# piezopiano.net
KiCad netlist of a schematic drawn in EAGLE
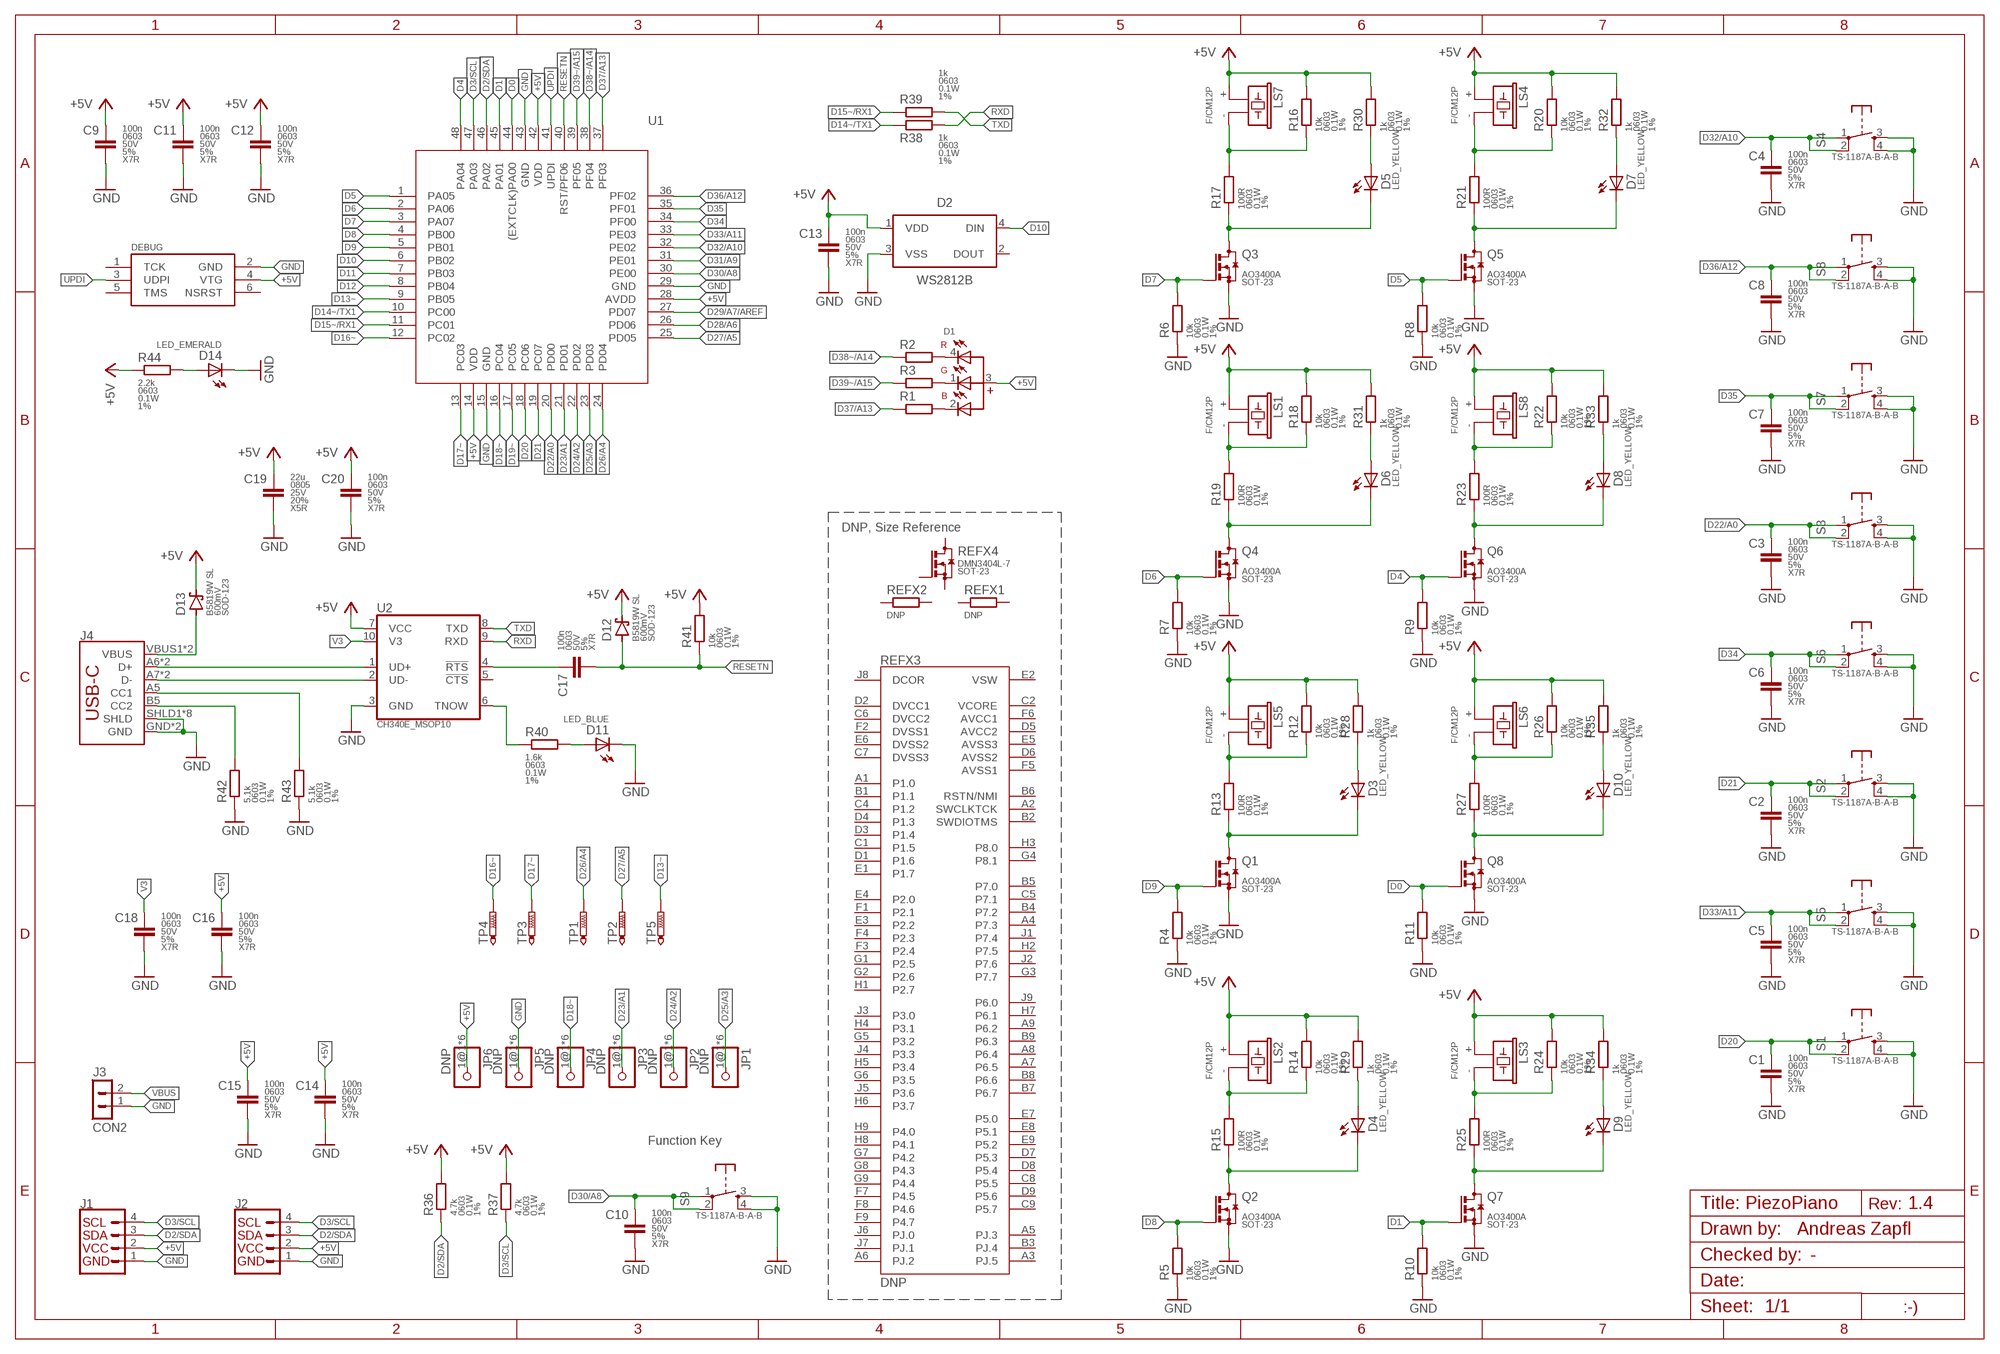
[diagram p0: schematic, sheet 1]

(export (version "E")
  (design (tool "Eeschema 10.0.6"))
  (components
    (comp (ref "C1")
      (value "100n")
      (footprint "eagle-import:C0603")
      (fields
        (field (name "PACKAGE-IN") "0603")
        (field (name "VOLTAGE") "50V")
        (field (name "TOLERANCE") "5%")
        (field (name "DIELECTRIC") "X7R")
        (field (name "MF") "Yageo")
        (field (name "MPN") "CC0603JRX7R9BB104")
      )
      (libsource (lib "eagle-import") (part "100NF-0603-50V-5%"))
    )
    (comp (ref "C2")
      (value "100n")
      (footprint "eagle-import:C0603")
      (fields
        (field (name "PACKAGE-IN") "0603")
        (field (name "VOLTAGE") "50V")
        (field (name "TOLERANCE") "5%")
        (field (name "DIELECTRIC") "X7R")
        (field (name "MF") "Yageo")
        (field (name "MPN") "CC0603JRX7R9BB104")
      )
      (libsource (lib "eagle-import") (part "100NF-0603-50V-5%"))
    )
    (comp (ref "C3")
      (value "100n")
      (footprint "eagle-import:C0603")
      (fields
        (field (name "PACKAGE-IN") "0603")
        (field (name "VOLTAGE") "50V")
        (field (name "TOLERANCE") "5%")
        (field (name "DIELECTRIC") "X7R")
        (field (name "MF") "Yageo")
        (field (name "MPN") "CC0603JRX7R9BB104")
      )
      (libsource (lib "eagle-import") (part "100NF-0603-50V-5%"))
    )
    (comp (ref "C4")
      (value "100n")
      (footprint "eagle-import:C0603")
      (fields
        (field (name "PACKAGE-IN") "0603")
        (field (name "VOLTAGE") "50V")
        (field (name "TOLERANCE") "5%")
        (field (name "DIELECTRIC") "X7R")
        (field (name "MF") "Yageo")
        (field (name "MPN") "CC0603JRX7R9BB104")
      )
      (libsource (lib "eagle-import") (part "100NF-0603-50V-5%"))
    )
    (comp (ref "C5")
      (value "100n")
      (footprint "eagle-import:C0603")
      (fields
        (field (name "PACKAGE-IN") "0603")
        (field (name "VOLTAGE") "50V")
        (field (name "TOLERANCE") "5%")
        (field (name "DIELECTRIC") "X7R")
        (field (name "MF") "Yageo")
        (field (name "MPN") "CC0603JRX7R9BB104")
      )
      (libsource (lib "eagle-import") (part "100NF-0603-50V-5%"))
    )
    (comp (ref "C6")
      (value "100n")
      (footprint "eagle-import:C0603")
      (fields
        (field (name "PACKAGE-IN") "0603")
        (field (name "VOLTAGE") "50V")
        (field (name "TOLERANCE") "5%")
        (field (name "DIELECTRIC") "X7R")
        (field (name "MF") "Yageo")
        (field (name "MPN") "CC0603JRX7R9BB104")
      )
      (libsource (lib "eagle-import") (part "100NF-0603-50V-5%"))
    )
    (comp (ref "C7")
      (value "100n")
      (footprint "eagle-import:C0603")
      (fields
        (field (name "PACKAGE-IN") "0603")
        (field (name "VOLTAGE") "50V")
        (field (name "TOLERANCE") "5%")
        (field (name "DIELECTRIC") "X7R")
        (field (name "MF") "Yageo")
        (field (name "MPN") "CC0603JRX7R9BB104")
      )
      (libsource (lib "eagle-import") (part "100NF-0603-50V-5%"))
    )
    (comp (ref "C8")
      (value "100n")
      (footprint "eagle-import:C0603")
      (fields
        (field (name "PACKAGE-IN") "0603")
        (field (name "VOLTAGE") "50V")
        (field (name "TOLERANCE") "5%")
        (field (name "DIELECTRIC") "X7R")
        (field (name "MF") "Yageo")
        (field (name "MPN") "CC0603JRX7R9BB104")
      )
      (libsource (lib "eagle-import") (part "100NF-0603-50V-5%"))
    )
    (comp (ref "C9")
      (value "100n")
      (footprint "eagle-import:C0603")
      (fields
        (field (name "PACKAGE-IN") "0603")
        (field (name "VOLTAGE") "50V")
        (field (name "TOLERANCE") "5%")
        (field (name "DIELECTRIC") "X7R")
        (field (name "MF") "Yageo")
        (field (name "MPN") "CC0603JRX7R9BB104")
      )
      (libsource (lib "eagle-import") (part "100NF-0603-50V-5%"))
    )
    (comp (ref "C10")
      (value "100n")
      (footprint "eagle-import:C0603")
      (fields
        (field (name "PACKAGE-IN") "0603")
        (field (name "VOLTAGE") "50V")
        (field (name "TOLERANCE") "5%")
        (field (name "DIELECTRIC") "X7R")
        (field (name "MF") "Yageo")
        (field (name "MPN") "CC0603JRX7R9BB104")
      )
      (libsource (lib "eagle-import") (part "100NF-0603-50V-5%"))
    )
    (comp (ref "C11")
      (value "100n")
      (footprint "eagle-import:C0603")
      (fields
        (field (name "PACKAGE-IN") "0603")
        (field (name "VOLTAGE") "50V")
        (field (name "TOLERANCE") "5%")
        (field (name "DIELECTRIC") "X7R")
        (field (name "MF") "Yageo")
        (field (name "MPN") "CC0603JRX7R9BB104")
      )
      (libsource (lib "eagle-import") (part "100NF-0603-50V-5%"))
    )
    (comp (ref "C12")
      (value "100n")
      (footprint "eagle-import:C0603")
      (fields
        (field (name "PACKAGE-IN") "0603")
        (field (name "VOLTAGE") "50V")
        (field (name "TOLERANCE") "5%")
        (field (name "DIELECTRIC") "X7R")
        (field (name "MF") "Yageo")
        (field (name "MPN") "CC0603JRX7R9BB104")
      )
      (libsource (lib "eagle-import") (part "100NF-0603-50V-5%"))
    )
    (comp (ref "C13")
      (value "100n")
      (footprint "eagle-import:C0603")
      (fields
        (field (name "PACKAGE-IN") "0603")
        (field (name "VOLTAGE") "50V")
        (field (name "TOLERANCE") "5%")
        (field (name "DIELECTRIC") "X7R")
        (field (name "MF") "Yageo")
        (field (name "MPN") "CC0603JRX7R9BB104")
      )
      (libsource (lib "eagle-import") (part "100NF-0603-50V-5%"))
    )
    (comp (ref "C14")
      (value "100n")
      (footprint "eagle-import:C0603")
      (fields
        (field (name "PACKAGE-IN") "0603")
        (field (name "VOLTAGE") "50V")
        (field (name "TOLERANCE") "5%")
        (field (name "DIELECTRIC") "X7R")
        (field (name "MF") "Yageo")
        (field (name "MPN") "CC0603JRX7R9BB104")
      )
      (libsource (lib "eagle-import") (part "100NF-0603-50V-5%"))
    )
    (comp (ref "C15")
      (value "100n")
      (footprint "eagle-import:C0603")
      (fields
        (field (name "PACKAGE-IN") "0603")
        (field (name "VOLTAGE") "50V")
        (field (name "TOLERANCE") "5%")
        (field (name "DIELECTRIC") "X7R")
        (field (name "MF") "Yageo")
        (field (name "MPN") "CC0603JRX7R9BB104")
      )
      (libsource (lib "eagle-import") (part "100NF-0603-50V-5%"))
    )
    (comp (ref "C16")
      (value "100n")
      (footprint "eagle-import:C0603")
      (fields
        (field (name "PACKAGE-IN") "0603")
        (field (name "VOLTAGE") "50V")
        (field (name "TOLERANCE") "5%")
        (field (name "DIELECTRIC") "X7R")
        (field (name "MF") "Yageo")
        (field (name "MPN") "CC0603JRX7R9BB104")
      )
      (libsource (lib "eagle-import") (part "100NF-0603-50V-5%"))
    )
    (comp (ref "C17")
      (value "100n")
      (footprint "eagle-import:C0603")
      (fields
        (field (name "PACKAGE-IN") "0603")
        (field (name "VOLTAGE") "50V")
        (field (name "TOLERANCE") "5%")
        (field (name "DIELECTRIC") "X7R")
        (field (name "MF") "Yageo")
        (field (name "MPN") "CC0603JRX7R9BB104")
      )
      (libsource (lib "eagle-import") (part "100NF-0603-50V-5%"))
    )
    (comp (ref "C18")
      (value "100n")
      (footprint "eagle-import:C0603")
      (fields
        (field (name "PACKAGE-IN") "0603")
        (field (name "VOLTAGE") "50V")
        (field (name "TOLERANCE") "5%")
        (field (name "DIELECTRIC") "X7R")
        (field (name "MF") "Yageo")
        (field (name "MPN") "CC0603JRX7R9BB104")
      )
      (libsource (lib "eagle-import") (part "100NF-0603-50V-5%"))
    )
    (comp (ref "C19")
      (value "22u")
      (footprint "eagle-import:C0805")
      (fields
        (field (name "PACKAGE-IN") "0805")
        (field (name "VOLTAGE") "25V")
        (field (name "TOLERANCE") "20%")
        (field (name "DIELECTRIC") "X5R")
        (field (name "MF") "Murata")
        (field (name "MPN") "GRM21BR61E226ME44L")
      )
      (libsource (lib "eagle-import") (part "22UF-0805-25V-20%"))
    )
    (comp (ref "C20")
      (value "100n")
      (footprint "eagle-import:C0603")
      (fields
        (field (name "PACKAGE-IN") "0603")
        (field (name "VOLTAGE") "50V")
        (field (name "TOLERANCE") "5%")
        (field (name "DIELECTRIC") "X7R")
        (field (name "MF") "Yageo")
        (field (name "MPN") "CC0603JRX7R9BB104")
      )
      (libsource (lib "eagle-import") (part "100NF-0603-50V-5%"))
    )
    (comp (ref "D1")
      (value "E6C1209RGBC3UDAM173000")
      (footprint "eagle-import:WL-SFCX_1210")
      (fields (field (name "MF") "EKINGLUX") (field (name "MPN") "E6C1209RGBC3UDA"))
      (libsource (lib "eagle-import") (part "E6C1209RGBC3UDAM173000"))
    )
    (comp (ref "D2")
      (value "WS2812B")
      (footprint "eagle-import:WS2812B")
      (fields (field (name "MANUFACTURER") "Worldsemi") (field (name "MPN") "WS2812B-B/W"))
      (libsource (lib "eagle-import") (part "WS2812B"))
    )
    (comp (ref "D3")
      (value "LED_YELLOW")
      (footprint "eagle-import:LEDC1608X55N_FLAT")
      (fields (field (name "MANUFACTURER") "Everlight Elec") (field (name "MPN") "19-213/Y2C-CQ2R2L/3T(CY)"))
      (libsource (lib "eagle-import") (part "CHIP-FLAT-Y_0603-0.55MM"))
    )
    (comp (ref "D4")
      (value "LED_YELLOW")
      (footprint "eagle-import:LEDC1608X55N_FLAT")
      (fields (field (name "MANUFACTURER") "Everlight Elec") (field (name "MPN") "19-213/Y2C-CQ2R2L/3T(CY)"))
      (libsource (lib "eagle-import") (part "CHIP-FLAT-Y_0603-0.55MM"))
    )
    (comp (ref "D5")
      (value "LED_YELLOW")
      (footprint "eagle-import:LEDC1608X55N_FLAT")
      (fields (field (name "MANUFACTURER") "Everlight Elec") (field (name "MPN") "19-213/Y2C-CQ2R2L/3T(CY)"))
      (libsource (lib "eagle-import") (part "CHIP-FLAT-Y_0603-0.55MM"))
    )
    (comp (ref "D6")
      (value "LED_YELLOW")
      (footprint "eagle-import:LEDC1608X55N_FLAT")
      (fields (field (name "MANUFACTURER") "Everlight Elec") (field (name "MPN") "19-213/Y2C-CQ2R2L/3T(CY)"))
      (libsource (lib "eagle-import") (part "CHIP-FLAT-Y_0603-0.55MM"))
    )
    (comp (ref "D7")
      (value "LED_YELLOW")
      (footprint "eagle-import:LEDC1608X55N_FLAT")
      (fields (field (name "MANUFACTURER") "Everlight Elec") (field (name "MPN") "19-213/Y2C-CQ2R2L/3T(CY)"))
      (libsource (lib "eagle-import") (part "CHIP-FLAT-Y_0603-0.55MM"))
    )
    (comp (ref "D8")
      (value "LED_YELLOW")
      (footprint "eagle-import:LEDC1608X55N_FLAT")
      (fields (field (name "MANUFACTURER") "Everlight Elec") (field (name "MPN") "19-213/Y2C-CQ2R2L/3T(CY)"))
      (libsource (lib "eagle-import") (part "CHIP-FLAT-Y_0603-0.55MM"))
    )
    (comp (ref "D9")
      (value "LED_YELLOW")
      (footprint "eagle-import:LEDC1608X55N_FLAT")
      (fields (field (name "MANUFACTURER") "Everlight Elec") (field (name "MPN") "19-213/Y2C-CQ2R2L/3T(CY)"))
      (libsource (lib "eagle-import") (part "CHIP-FLAT-Y_0603-0.55MM"))
    )
    (comp (ref "D10")
      (value "LED_YELLOW")
      (footprint "eagle-import:LEDC1608X55N_FLAT")
      (fields (field (name "MANUFACTURER") "Everlight Elec") (field (name "MPN") "19-213/Y2C-CQ2R2L/3T(CY)"))
      (libsource (lib "eagle-import") (part "CHIP-FLAT-Y_0603-0.55MM"))
    )
    (comp (ref "D11")
      (value "LED_BLUE")
      (footprint "eagle-import:LEDC1608X55N_FLAT")
      (fields (field (name "MANUFACTURER") "Everlight Elec") (field (name "MPN") "19-217/GHC-YR1S2/3T"))
      (libsource (lib "eagle-import") (part "CHIP-FLAT-B_0603-0.55MM"))
    )
    (comp (ref "D12")
      (value "B5819WSL")
      (footprint "eagle-import:SOD123")
      (fields
        (field (name "MPN") "B5819W SL")
        (field (name "VOLTAGE_FORWARD") "600mV")
        (field (name "PACKAGE") "SOD-123")
        (field (name "MF") "Changjiang Electronics Tech (CJ)")
      )
      (libsource (lib "eagle-import") (part "B5819WSL"))
    )
    (comp (ref "D13")
      (value "B5819WSL")
      (footprint "eagle-import:SOD123")
      (fields
        (field (name "MPN") "B5819W SL")
        (field (name "VOLTAGE_FORWARD") "600mV")
        (field (name "PACKAGE") "SOD-123")
        (field (name "MF") "Changjiang Electronics Tech (CJ)")
      )
      (libsource (lib "eagle-import") (part "B5819WSL"))
    )
    (comp (ref "D14")
      (value "LED_EMERALD")
      (footprint "eagle-import:LEDC1608X55N_FLAT")
      (fields (field (name "MANUFACTURER") "Everlight Elec") (field (name "MPN") "19-217/BHC-ZL1M2RY/3T"))
      (libsource (lib "eagle-import") (part "CHIP-FLAT-G_0603-0.55MM"))
    )
    (comp (ref "DEBUG")
      (value "DNP")
      (footprint "eagle-import:490107670612_DEBUGGING")
      (libsource (lib "eagle-import") (part "AVR-UPDI-6-SKEDD"))
    )
    (comp (ref "J1")
      (value "QWIIC_CONNECTORJS-1MM")
      (footprint "eagle-import:1X04_1MM_RA")
      (fields (field (name "MF") "BOOMELE") (field (name "MPN") "C145956"))
      (libsource (lib "eagle-import") (part "QWIIC_CONNECTORJS-1MM"))
    )
    (comp (ref "J2")
      (value "QWIIC_CONNECTORJS-1MM")
      (footprint "eagle-import:1X04_1MM_RA")
      (fields (field (name "MF") "BOOMELE") (field (name "MPN") "C145956"))
      (libsource (lib "eagle-import") (part "QWIIC_CONNECTORJS-1MM"))
    )
    (comp (ref "J3")
      (value "CON2")
      (footprint "eagle-import:H2-2.54")
      (libsource (lib "eagle-import") (part "CON2"))
    )
    (comp (ref "J4")
      (value "USB_C2-LAYER")
      (footprint "eagle-import:USB-C-16P")
      (fields (field (name "MF") "YIYUAN") (field (name "MPN") "YTC-TC16S-23"))
      (libsource (lib "eagle-import") (part "USB_C2-LAYER"))
    )
    (comp (ref "JP1")
      (value "DNP")
      (footprint "eagle-import:1X01")
      (libsource (lib "eagle-import") (part "PINROW-1X5"))
    )
    (comp (ref "JP2")
      (value "DNP")
      (footprint "eagle-import:1X01")
      (libsource (lib "eagle-import") (part "PINROW-1X5"))
    )
    (comp (ref "JP3")
      (value "DNP")
      (footprint "eagle-import:1X01")
      (libsource (lib "eagle-import") (part "PINROW-1X5"))
    )
    (comp (ref "JP4")
      (value "DNP")
      (footprint "eagle-import:1X01")
      (libsource (lib "eagle-import") (part "PINROW-1X5"))
    )
    (comp (ref "JP5")
      (value "DNP")
      (footprint "eagle-import:1X01")
      (libsource (lib "eagle-import") (part "PINROW-1X5"))
    )
    (comp (ref "JP6")
      (value "DNP")
      (footprint "eagle-import:1X01")
      (libsource (lib "eagle-import") (part "PINROW-1X5"))
    )
    (comp (ref "LS1")
      (value "F/CM12P")
      (footprint "eagle-import:CM12P_5.0P")
      (fields (field (name "MF") "ZLFY") (field (name "MPN") "ZL-YDW1207-4005PA-5.0"))
      (libsource (lib "eagle-import") (part "F/CM12P"))
    )
    (comp (ref "LS2")
      (value "F/CM12P")
      (footprint "eagle-import:CM12P_5.0P")
      (fields (field (name "MF") "ZLFY") (field (name "MPN") "ZL-YDW1207-4005PA-5.0"))
      (libsource (lib "eagle-import") (part "F/CM12P"))
    )
    (comp (ref "LS3")
      (value "F/CM12P")
      (footprint "eagle-import:CM12P_5.0P")
      (fields (field (name "MF") "ZLFY") (field (name "MPN") "ZL-YDW1207-4005PA-5.0"))
      (libsource (lib "eagle-import") (part "F/CM12P"))
    )
    (comp (ref "LS4")
      (value "F/CM12P")
      (footprint "eagle-import:CM12P_5.0P")
      (fields (field (name "MF") "ZLFY") (field (name "MPN") "ZL-YDW1207-4005PA-5.0"))
      (libsource (lib "eagle-import") (part "F/CM12P"))
    )
    (comp (ref "LS5")
      (value "F/CM12P")
      (footprint "eagle-import:CM12P_5.0P")
      (fields (field (name "MF") "ZLFY") (field (name "MPN") "ZL-YDW1207-4005PA-5.0"))
      (libsource (lib "eagle-import") (part "F/CM12P"))
    )
    (comp (ref "LS6")
      (value "F/CM12P")
      (footprint "eagle-import:CM12P_5.0P")
      (fields (field (name "MF") "ZLFY") (field (name "MPN") "ZL-YDW1207-4005PA-5.0"))
      (libsource (lib "eagle-import") (part "F/CM12P"))
    )
    (comp (ref "LS7")
      (value "F/CM12P")
      (footprint "eagle-import:CM12P_5.0P")
      (fields (field (name "MF") "ZLFY") (field (name "MPN") "ZL-YDW1207-4005PA-5.0"))
      (libsource (lib "eagle-import") (part "F/CM12P"))
    )
    (comp (ref "LS8")
      (value "F/CM12P")
      (footprint "eagle-import:CM12P_5.0P")
      (fields (field (name "MF") "ZLFY") (field (name "MPN") "ZL-YDW1207-4005PA-5.0"))
      (libsource (lib "eagle-import") (part "F/CM12P"))
    )
    (comp (ref "Q1")
      (value "AO3400A")
      (footprint "eagle-import:SOT23")
      (fields
        (field (name "MPN") "AO3400A")
        (field (name "PACKAGE") "SOT-23")
        (field (name "MF") "Alpha & Omega Semicon")
      )
      (libsource (lib "eagle-import") (part "AO3400A"))
    )
    (comp (ref "Q2")
      (value "AO3400A")
      (footprint "eagle-import:SOT23")
      (fields
        (field (name "MPN") "AO3400A")
        (field (name "PACKAGE") "SOT-23")
        (field (name "MF") "Alpha & Omega Semicon")
      )
      (libsource (lib "eagle-import") (part "AO3400A"))
    )
    (comp (ref "Q3")
      (value "AO3400A")
      (footprint "eagle-import:SOT23")
      (fields
        (field (name "MPN") "AO3400A")
        (field (name "PACKAGE") "SOT-23")
        (field (name "MF") "Alpha & Omega Semicon")
      )
      (libsource (lib "eagle-import") (part "AO3400A"))
    )
    (comp (ref "Q4")
      (value "AO3400A")
      (footprint "eagle-import:SOT23")
      (fields
        (field (name "MPN") "AO3400A")
        (field (name "PACKAGE") "SOT-23")
        (field (name "MF") "Alpha & Omega Semicon")
      )
      (libsource (lib "eagle-import") (part "AO3400A"))
    )
    (comp (ref "Q5")
      (value "AO3400A")
      (footprint "eagle-import:SOT23")
      (fields
        (field (name "MPN") "AO3400A")
        (field (name "PACKAGE") "SOT-23")
        (field (name "MF") "Alpha & Omega Semicon")
      )
      (libsource (lib "eagle-import") (part "AO3400A"))
    )
    (comp (ref "Q6")
      (value "AO3400A")
      (footprint "eagle-import:SOT23")
      (fields
        (field (name "MPN") "AO3400A")
        (field (name "PACKAGE") "SOT-23")
        (field (name "MF") "Alpha & Omega Semicon")
      )
      (libsource (lib "eagle-import") (part "AO3400A"))
    )
    (comp (ref "Q7")
      (value "AO3400A")
      (footprint "eagle-import:SOT23")
      (fields
        (field (name "MPN") "AO3400A")
        (field (name "PACKAGE") "SOT-23")
        (field (name "MF") "Alpha & Omega Semicon")
      )
      (libsource (lib "eagle-import") (part "AO3400A"))
    )
    (comp (ref "Q8")
      (value "AO3400A")
      (footprint "eagle-import:SOT23")
      (fields
        (field (name "MPN") "AO3400A")
        (field (name "PACKAGE") "SOT-23")
        (field (name "MF") "Alpha & Omega Semicon")
      )
      (libsource (lib "eagle-import") (part "AO3400A"))
    )
    (comp (ref "R1")
      (value "1.6k")
      (footprint "eagle-import:R0603")
      (fields (field (name "POWER") "0.1W") (field (name "TOLERANCE") "1%") (field (name "MF") "Yageo"))
      (libsource (lib "eagle-import") (part "1.6KOHM-0603-1/10W-1%"))
    )
    (comp (ref "R2")
      (value "1k")
      (footprint "eagle-import:R0603")
      (fields (field (name "POWER") "0.1W") (field (name "TOLERANCE") "1%") (field (name "MF") "Yageo"))
      (libsource (lib "eagle-import") (part "1KOHM-0603-1/10W-1%"))
    )
    (comp (ref "R3")
      (value "2.2k")
      (footprint "eagle-import:R0603")
      (fields (field (name "POWER") "0.1W") (field (name "TOLERANCE") "1%") (field (name "MF") "Yageo"))
      (libsource (lib "eagle-import") (part "2.2KOHM-0603-1/10W-1%"))
    )
    (comp (ref "R4")
      (value "10k")
      (footprint "eagle-import:R0603")
      (fields
        (field (name "PACKAGE-IN") "0603")
        (field (name "POWER") "0.1W")
        (field (name "TOLERANCE") "1%")
        (field (name "MF") "Yageo")
        (field (name "MPN") "RC0603FR-0710KL")
        (field (name "VOLTAGE") "75V")
      )
      (libsource (lib "eagle-import") (part "10KOHM-0603-1/10W-1%"))
    )
    (comp (ref "R5")
      (value "10k")
      (footprint "eagle-import:R0603")
      (fields
        (field (name "PACKAGE-IN") "0603")
        (field (name "POWER") "0.1W")
        (field (name "TOLERANCE") "1%")
        (field (name "MF") "Yageo")
        (field (name "MPN") "RC0603FR-0710KL")
        (field (name "VOLTAGE") "75V")
      )
      (libsource (lib "eagle-import") (part "10KOHM-0603-1/10W-1%"))
    )
    (comp (ref "R6")
      (value "10k")
      (footprint "eagle-import:R0603")
      (fields
        (field (name "PACKAGE-IN") "0603")
        (field (name "POWER") "0.1W")
        (field (name "TOLERANCE") "1%")
        (field (name "MF") "Yageo")
        (field (name "MPN") "RC0603FR-0710KL")
        (field (name "VOLTAGE") "75V")
      )
      (libsource (lib "eagle-import") (part "10KOHM-0603-1/10W-1%"))
    )
    (comp (ref "R7")
      (value "10k")
      (footprint "eagle-import:R0603")
      (fields
        (field (name "PACKAGE-IN") "0603")
        (field (name "POWER") "0.1W")
        (field (name "TOLERANCE") "1%")
        (field (name "MF") "Yageo")
        (field (name "MPN") "RC0603FR-0710KL")
        (field (name "VOLTAGE") "75V")
      )
      (libsource (lib "eagle-import") (part "10KOHM-0603-1/10W-1%"))
    )
    (comp (ref "R8")
      (value "10k")
      (footprint "eagle-import:R0603")
      (fields
        (field (name "PACKAGE-IN") "0603")
        (field (name "POWER") "0.1W")
        (field (name "TOLERANCE") "1%")
        (field (name "MF") "Yageo")
        (field (name "MPN") "RC0603FR-0710KL")
        (field (name "VOLTAGE") "75V")
      )
      (libsource (lib "eagle-import") (part "10KOHM-0603-1/10W-1%"))
    )
    (comp (ref "R9")
      (value "10k")
      (footprint "eagle-import:R0603")
      (fields
        (field (name "PACKAGE-IN") "0603")
        (field (name "POWER") "0.1W")
        (field (name "TOLERANCE") "1%")
        (field (name "MF") "Yageo")
        (field (name "MPN") "RC0603FR-0710KL")
        (field (name "VOLTAGE") "75V")
      )
      (libsource (lib "eagle-import") (part "10KOHM-0603-1/10W-1%"))
    )
    (comp (ref "R10")
      (value "10k")
      (footprint "eagle-import:R0603")
      (fields
        (field (name "PACKAGE-IN") "0603")
        (field (name "POWER") "0.1W")
        (field (name "TOLERANCE") "1%")
        (field (name "MF") "Yageo")
        (field (name "MPN") "RC0603FR-0710KL")
        (field (name "VOLTAGE") "75V")
      )
      (libsource (lib "eagle-import") (part "10KOHM-0603-1/10W-1%"))
    )
    (comp (ref "R11")
      (value "10k")
      (footprint "eagle-import:R0603")
      (fields
        (field (name "PACKAGE-IN") "0603")
        (field (name "POWER") "0.1W")
        (field (name "TOLERANCE") "1%")
        (field (name "MF") "Yageo")
        (field (name "MPN") "RC0603FR-0710KL")
        (field (name "VOLTAGE") "75V")
      )
      (libsource (lib "eagle-import") (part "10KOHM-0603-1/10W-1%"))
    )
    (comp (ref "R12")
      (value "10k")
      (footprint "eagle-import:R0603")
      (fields
        (field (name "PACKAGE-IN") "0603")
        (field (name "POWER") "0.1W")
        (field (name "TOLERANCE") "1%")
        (field (name "MF") "Yageo")
        (field (name "MPN") "RC0603FR-0710KL")
        (field (name "VOLTAGE") "75V")
      )
      (libsource (lib "eagle-import") (part "10KOHM-0603-1/10W-1%"))
    )
    (comp (ref "R13")
      (value "100R")
      (footprint "eagle-import:R0603")
      (fields
        (field (name "PACKAGE-IN") "0603")
        (field (name "POWER") "0.1W")
        (field (name "TOLERANCE") "1%")
        (field (name "MF") "Yageo")
        (field (name "MPN") "RC0603FR-07100RL")
        (field (name "VOLTAGE") "75V")
      )
      (libsource (lib "eagle-import") (part "100OHM-0603-1/10W-1%"))
    )
    (comp (ref "R14")
      (value "10k")
      (footprint "eagle-import:R0603")
      (fields
        (field (name "PACKAGE-IN") "0603")
        (field (name "POWER") "0.1W")
        (field (name "TOLERANCE") "1%")
        (field (name "MF") "Yageo")
        (field (name "MPN") "RC0603FR-0710KL")
        (field (name "VOLTAGE") "75V")
      )
      (libsource (lib "eagle-import") (part "10KOHM-0603-1/10W-1%"))
    )
    (comp (ref "R15")
      (value "100R")
      (footprint "eagle-import:R0603")
      (fields
        (field (name "PACKAGE-IN") "0603")
        (field (name "POWER") "0.1W")
        (field (name "TOLERANCE") "1%")
        (field (name "MF") "Yageo")
        (field (name "MPN") "RC0603FR-07100RL")
        (field (name "VOLTAGE") "75V")
      )
      (libsource (lib "eagle-import") (part "100OHM-0603-1/10W-1%"))
    )
    (comp (ref "R16")
      (value "10k")
      (footprint "eagle-import:R0603")
      (fields
        (field (name "PACKAGE-IN") "0603")
        (field (name "POWER") "0.1W")
        (field (name "TOLERANCE") "1%")
        (field (name "MF") "Yageo")
        (field (name "MPN") "RC0603FR-0710KL")
        (field (name "VOLTAGE") "75V")
      )
      (libsource (lib "eagle-import") (part "10KOHM-0603-1/10W-1%"))
    )
    (comp (ref "R17")
      (value "100R")
      (footprint "eagle-import:R0603")
      (fields
        (field (name "PACKAGE-IN") "0603")
        (field (name "POWER") "0.1W")
        (field (name "TOLERANCE") "1%")
        (field (name "MF") "Yageo")
        (field (name "MPN") "RC0603FR-07100RL")
        (field (name "VOLTAGE") "75V")
      )
      (libsource (lib "eagle-import") (part "100OHM-0603-1/10W-1%"))
    )
    (comp (ref "R18")
      (value "10k")
      (footprint "eagle-import:R0603")
      (fields
        (field (name "PACKAGE-IN") "0603")
        (field (name "POWER") "0.1W")
        (field (name "TOLERANCE") "1%")
        (field (name "MF") "Yageo")
        (field (name "MPN") "RC0603FR-0710KL")
        (field (name "VOLTAGE") "75V")
      )
      (libsource (lib "eagle-import") (part "10KOHM-0603-1/10W-1%"))
    )
    (comp (ref "R19")
      (value "100R")
      (footprint "eagle-import:R0603")
      (fields
        (field (name "PACKAGE-IN") "0603")
        (field (name "POWER") "0.1W")
        (field (name "TOLERANCE") "1%")
        (field (name "MF") "Yageo")
        (field (name "MPN") "RC0603FR-07100RL")
        (field (name "VOLTAGE") "75V")
      )
      (libsource (lib "eagle-import") (part "100OHM-0603-1/10W-1%"))
    )
    (comp (ref "R20")
      (value "10k")
      (footprint "eagle-import:R0603")
      (fields
        (field (name "PACKAGE-IN") "0603")
        (field (name "POWER") "0.1W")
        (field (name "TOLERANCE") "1%")
        (field (name "MF") "Yageo")
        (field (name "MPN") "RC0603FR-0710KL")
        (field (name "VOLTAGE") "75V")
      )
      (libsource (lib "eagle-import") (part "10KOHM-0603-1/10W-1%"))
    )
    (comp (ref "R21")
      (value "100R")
      (footprint "eagle-import:R0603")
      (fields
        (field (name "PACKAGE-IN") "0603")
        (field (name "POWER") "0.1W")
        (field (name "TOLERANCE") "1%")
        (field (name "MF") "Yageo")
        (field (name "MPN") "RC0603FR-07100RL")
        (field (name "VOLTAGE") "75V")
      )
      (libsource (lib "eagle-import") (part "100OHM-0603-1/10W-1%"))
    )
    (comp (ref "R22")
      (value "10k")
      (footprint "eagle-import:R0603")
      (fields
        (field (name "PACKAGE-IN") "0603")
        (field (name "POWER") "0.1W")
        (field (name "TOLERANCE") "1%")
        (field (name "MF") "Yageo")
        (field (name "MPN") "RC0603FR-0710KL")
        (field (name "VOLTAGE") "75V")
      )
      (libsource (lib "eagle-import") (part "10KOHM-0603-1/10W-1%"))
    )
    (comp (ref "R23")
      (value "100R")
      (footprint "eagle-import:R0603")
      (fields
        (field (name "PACKAGE-IN") "0603")
        (field (name "POWER") "0.1W")
        (field (name "TOLERANCE") "1%")
        (field (name "MF") "Yageo")
        (field (name "MPN") "RC0603FR-07100RL")
        (field (name "VOLTAGE") "75V")
      )
      (libsource (lib "eagle-import") (part "100OHM-0603-1/10W-1%"))
    )
    (comp (ref "R24")
      (value "10k")
      (footprint "eagle-import:R0603")
      (fields
        (field (name "PACKAGE-IN") "0603")
        (field (name "POWER") "0.1W")
        (field (name "TOLERANCE") "1%")
        (field (name "MF") "Yageo")
        (field (name "MPN") "RC0603FR-0710KL")
        (field (name "VOLTAGE") "75V")
      )
      (libsource (lib "eagle-import") (part "10KOHM-0603-1/10W-1%"))
    )
    (comp (ref "R25")
      (value "100R")
      (footprint "eagle-import:R0603")
      (fields
        (field (name "PACKAGE-IN") "0603")
        (field (name "POWER") "0.1W")
        (field (name "TOLERANCE") "1%")
        (field (name "MF") "Yageo")
        (field (name "MPN") "RC0603FR-07100RL")
        (field (name "VOLTAGE") "75V")
      )
      (libsource (lib "eagle-import") (part "100OHM-0603-1/10W-1%"))
    )
    (comp (ref "R26")
      (value "10k")
      (footprint "eagle-import:R0603")
      (fields
        (field (name "PACKAGE-IN") "0603")
        (field (name "POWER") "0.1W")
        (field (name "TOLERANCE") "1%")
        (field (name "MF") "Yageo")
        (field (name "MPN") "RC0603FR-0710KL")
        (field (name "VOLTAGE") "75V")
      )
      (libsource (lib "eagle-import") (part "10KOHM-0603-1/10W-1%"))
    )
    (comp (ref "R27")
      (value "100R")
      (footprint "eagle-import:R0603")
      (fields
        (field (name "PACKAGE-IN") "0603")
        (field (name "POWER") "0.1W")
        (field (name "TOLERANCE") "1%")
        (field (name "MF") "Yageo")
        (field (name "MPN") "RC0603FR-07100RL")
        (field (name "VOLTAGE") "75V")
      )
      (libsource (lib "eagle-import") (part "100OHM-0603-1/10W-1%"))
    )
    (comp (ref "R28")
      (value "1k")
      (footprint "eagle-import:R0603")
      (fields
        (field (name "PACKAGE-IN") "0603")
        (field (name "POWER") "0.1W")
        (field (name "TOLERANCE") "1%")
        (field (name "MF") "Yageo")
        (field (name "MPN") "RC0603FR-071KL")
        (field (name "VOLTAGE") "75V")
      )
      (libsource (lib "eagle-import") (part "1KOHM-0603-1/10W-1%"))
    )
    (comp (ref "R29")
      (value "1k")
      (footprint "eagle-import:R0603")
      (fields
        (field (name "PACKAGE-IN") "0603")
        (field (name "POWER") "0.1W")
        (field (name "TOLERANCE") "1%")
        (field (name "MF") "Yageo")
        (field (name "MPN") "RC0603FR-071KL")
        (field (name "VOLTAGE") "75V")
      )
      (libsource (lib "eagle-import") (part "1KOHM-0603-1/10W-1%"))
    )
    (comp (ref "R30")
      (value "1k")
      (footprint "eagle-import:R0603")
      (fields
        (field (name "PACKAGE-IN") "0603")
        (field (name "POWER") "0.1W")
        (field (name "TOLERANCE") "1%")
        (field (name "MF") "Yageo")
        (field (name "MPN") "RC0603FR-071KL")
        (field (name "VOLTAGE") "75V")
      )
      (libsource (lib "eagle-import") (part "1KOHM-0603-1/10W-1%"))
    )
    (comp (ref "R31")
      (value "1k")
      (footprint "eagle-import:R0603")
      (fields
        (field (name "PACKAGE-IN") "0603")
        (field (name "POWER") "0.1W")
        (field (name "TOLERANCE") "1%")
        (field (name "MF") "Yageo")
        (field (name "MPN") "RC0603FR-071KL")
        (field (name "VOLTAGE") "75V")
      )
      (libsource (lib "eagle-import") (part "1KOHM-0603-1/10W-1%"))
    )
    (comp (ref "R32")
      (value "1k")
      (footprint "eagle-import:R0603")
      (fields
        (field (name "PACKAGE-IN") "0603")
        (field (name "POWER") "0.1W")
        (field (name "TOLERANCE") "1%")
        (field (name "MF") "Yageo")
        (field (name "MPN") "RC0603FR-071KL")
        (field (name "VOLTAGE") "75V")
      )
      (libsource (lib "eagle-import") (part "1KOHM-0603-1/10W-1%"))
    )
    (comp (ref "R33")
      (value "1k")
      (footprint "eagle-import:R0603")
      (fields
        (field (name "PACKAGE-IN") "0603")
        (field (name "POWER") "0.1W")
        (field (name "TOLERANCE") "1%")
        (field (name "MF") "Yageo")
        (field (name "MPN") "RC0603FR-071KL")
        (field (name "VOLTAGE") "75V")
      )
      (libsource (lib "eagle-import") (part "1KOHM-0603-1/10W-1%"))
    )
    (comp (ref "R34")
      (value "1k")
      (footprint "eagle-import:R0603")
      (fields
        (field (name "PACKAGE-IN") "0603")
        (field (name "POWER") "0.1W")
        (field (name "TOLERANCE") "1%")
        (field (name "MF") "Yageo")
        (field (name "MPN") "RC0603FR-071KL")
        (field (name "VOLTAGE") "75V")
      )
      (libsource (lib "eagle-import") (part "1KOHM-0603-1/10W-1%"))
    )
    (comp (ref "R35")
      (value "1k")
      (footprint "eagle-import:R0603")
      (fields
        (field (name "PACKAGE-IN") "0603")
        (field (name "POWER") "0.1W")
        (field (name "TOLERANCE") "1%")
        (field (name "MF") "Yageo")
        (field (name "MPN") "RC0603FR-071KL")
        (field (name "VOLTAGE") "75V")
      )
      (libsource (lib "eagle-import") (part "1KOHM-0603-1/10W-1%"))
    )
    (comp (ref "R36")
      (value "4.7k")
      (footprint "eagle-import:R0603")
      (fields
        (field (name "PACKAGE-IN") "0603")
        (field (name "POWER") "0.1W")
        (field (name "TOLERANCE") "1%")
        (field (name "MF") "Yageo")
        (field (name "MPN") "RC0603FR-074K7L")
        (field (name "VOLTAGE") "75V")
      )
      (libsource (lib "eagle-import") (part "4.7KOHM-0603-1/10W-1%"))
    )
    (comp (ref "R37")
      (value "4.7k")
      (footprint "eagle-import:R0603")
      (fields
        (field (name "PACKAGE-IN") "0603")
        (field (name "POWER") "0.1W")
        (field (name "TOLERANCE") "1%")
        (field (name "MF") "Yageo")
        (field (name "MPN") "RC0603FR-074K7L")
        (field (name "VOLTAGE") "75V")
      )
      (libsource (lib "eagle-import") (part "4.7KOHM-0603-1/10W-1%"))
    )
    (comp (ref "R38")
      (value "1k")
      (footprint "eagle-import:R0603")
      (fields
        (field (name "PACKAGE-IN") "0603")
        (field (name "POWER") "0.1W")
        (field (name "TOLERANCE") "1%")
        (field (name "MF") "Yageo")
        (field (name "MPN") "RC0603FR-071KL")
        (field (name "VOLTAGE") "75V")
      )
      (libsource (lib "eagle-import") (part "1KOHM-0603-1/10W-1%"))
    )
    (comp (ref "R39")
      (value "1k")
      (footprint "eagle-import:R0603")
      (fields
        (field (name "PACKAGE-IN") "0603")
        (field (name "POWER") "0.1W")
        (field (name "TOLERANCE") "1%")
        (field (name "MF") "Yageo")
        (field (name "MPN") "RC0603FR-071KL")
        (field (name "VOLTAGE") "75V")
      )
      (libsource (lib "eagle-import") (part "1KOHM-0603-1/10W-1%"))
    )
    (comp (ref "R40")
      (value "1.6k")
      (footprint "eagle-import:R0603")
      (fields
        (field (name "PACKAGE-IN") "0603")
        (field (name "POWER") "0.1W")
        (field (name "TOLERANCE") "1%")
        (field (name "MF") "Yageo")
        (field (name "MPN") "RC0603FR-071K6L")
        (field (name "VOLTAGE") "75V")
      )
      (libsource (lib "eagle-import") (part "1.6KOHM-0603-1/10W-1%"))
    )
    (comp (ref "R41")
      (value "10k")
      (footprint "eagle-import:R0603")
      (fields
        (field (name "PACKAGE-IN") "0603")
        (field (name "POWER") "0.1W")
        (field (name "TOLERANCE") "1%")
        (field (name "MF") "Yageo")
        (field (name "MPN") "RC0603FR-0710KL")
        (field (name "VOLTAGE") "75V")
      )
      (libsource (lib "eagle-import") (part "10KOHM-0603-1/10W-1%"))
    )
    (comp (ref "R42")
      (value "5.1k")
      (footprint "eagle-import:R0603")
      (fields
        (field (name "PACKAGE-IN") "0603")
        (field (name "POWER") "0.1W")
        (field (name "TOLERANCE") "1%")
        (field (name "MF") "Yageo")
        (field (name "MPN") "RC0603FR-075K1L")
        (field (name "VOLTAGE") "75V")
      )
      (libsource (lib "eagle-import") (part "5.1KOHM-0603-1/10W-1%"))
    )
    (comp (ref "R43")
      (value "5.1k")
      (footprint "eagle-import:R0603")
      (fields
        (field (name "PACKAGE-IN") "0603")
        (field (name "POWER") "0.1W")
        (field (name "TOLERANCE") "1%")
        (field (name "MF") "Yageo")
        (field (name "MPN") "RC0603FR-075K1L")
        (field (name "VOLTAGE") "75V")
      )
      (libsource (lib "eagle-import") (part "5.1KOHM-0603-1/10W-1%"))
    )
    (comp (ref "R44")
      (value "2.2k")
      (footprint "eagle-import:R0603")
      (fields
        (field (name "PACKAGE-IN") "0603")
        (field (name "POWER") "0.1W")
        (field (name "TOLERANCE") "1%")
        (field (name "MF") "Yageo")
        (field (name "MPN") "RC0603FR-072K2L")
        (field (name "VOLTAGE") "75V")
      )
      (libsource (lib "eagle-import") (part "2.2KOHM-0603-1/10W-1%"))
    )
    (comp (ref "REFX1")
      (value "DNP")
      (footprint "eagle-import:R0603")
      (libsource (lib "eagle-import") (part "DNP-0603"))
    )
    (comp (ref "REFX2")
      (value "DNP")
      (footprint "eagle-import:R0805")
      (libsource (lib "eagle-import") (part "DNP-0805"))
    )
    (comp (ref "REFX3")
      (value "DNP")
      (footprint "eagle-import:BGA80")
      (fields
        (field (name "DIGIKEY_PARTNO") "296-45566-6-ND")
        (field (name "MANUFACTURER") "Texas Instruments")
        (field (name "MPN") "MSP432P401RIZXHR")
        (field (name "CREATED_BY") "PCBLayout.com")
      )
      (libsource (lib "eagle-import") (part "MSP432P401RIZXHR"))
    )
    (comp (ref "REFX4")
      (value "DNP")
      (footprint "eagle-import:SOT23")
      (fields
        (field (name "MPN") "DMN3404L-7")
        (field (name "PACKAGE") "SOT-23")
        (field (name "MF") "Diodes Incorporated")
      )
      (libsource (lib "eagle-import") (part "DMN3404L"))
    )
    (comp (ref "S1")
      (value "TS-1187A-B-A-B")
      (footprint "eagle-import:TACTILE_SWITCH_SMD_5.2MM")
      (fields (field (name "MF") "XKB Connectivity"))
      (libsource (lib "eagle-import") (part "TS-1187A-B-A-B"))
    )
    (comp (ref "S2")
      (value "TS-1187A-B-A-B")
      (footprint "eagle-import:TACTILE_SWITCH_SMD_5.2MM")
      (fields (field (name "MF") "XKB Connectivity"))
      (libsource (lib "eagle-import") (part "TS-1187A-B-A-B"))
    )
    (comp (ref "S3")
      (value "TS-1187A-B-A-B")
      (footprint "eagle-import:TACTILE_SWITCH_SMD_5.2MM")
      (fields (field (name "MF") "XKB Connectivity"))
      (libsource (lib "eagle-import") (part "TS-1187A-B-A-B"))
    )
    (comp (ref "S4")
      (value "TS-1187A-B-A-B")
      (footprint "eagle-import:TACTILE_SWITCH_SMD_5.2MM")
      (fields (field (name "MF") "XKB Connectivity"))
      (libsource (lib "eagle-import") (part "TS-1187A-B-A-B"))
    )
    (comp (ref "S5")
      (value "TS-1187A-B-A-B")
      (footprint "eagle-import:TACTILE_SWITCH_SMD_5.2MM")
      (fields (field (name "MF") "XKB Connectivity"))
      (libsource (lib "eagle-import") (part "TS-1187A-B-A-B"))
    )
    (comp (ref "S6")
      (value "TS-1187A-B-A-B")
      (footprint "eagle-import:TACTILE_SWITCH_SMD_5.2MM")
      (fields (field (name "MF") "XKB Connectivity"))
      (libsource (lib "eagle-import") (part "TS-1187A-B-A-B"))
    )
    (comp (ref "S7")
      (value "TS-1187A-B-A-B")
      (footprint "eagle-import:TACTILE_SWITCH_SMD_5.2MM")
      (fields (field (name "MF") "XKB Connectivity"))
      (libsource (lib "eagle-import") (part "TS-1187A-B-A-B"))
    )
    (comp (ref "S8")
      (value "TS-1187A-B-A-B")
      (footprint "eagle-import:TACTILE_SWITCH_SMD_5.2MM")
      (fields (field (name "MF") "XKB Connectivity"))
      (libsource (lib "eagle-import") (part "TS-1187A-B-A-B"))
    )
    (comp (ref "S9")
      (value "TS-1187A-B-A-B")
      (footprint "eagle-import:TACTILE_SWITCH_SMD_5.2MM")
      (fields (field (name "MF") "XKB Connectivity"))
      (libsource (lib "eagle-import") (part "TS-1187A-B-A-B"))
    )
    (comp (ref "TP1")
      (value "PTR1B1,27")
      (footprint "eagle-import:B1,27")
      (libsource (lib "eagle-import") (part "PTR1B1,27"))
    )
    (comp (ref "TP2")
      (value "PTR1B1,27")
      (footprint "eagle-import:B1,27")
      (libsource (lib "eagle-import") (part "PTR1B1,27"))
    )
    (comp (ref "TP3")
      (value "PTR1B1,27")
      (footprint "eagle-import:B1,27")
      (libsource (lib "eagle-import") (part "PTR1B1,27"))
    )
    (comp (ref "TP4")
      (value "PTR1B1,27")
      (footprint "eagle-import:B1,27")
      (libsource (lib "eagle-import") (part "PTR1B1,27"))
    )
    (comp (ref "TP5")
      (value "PTR1B1,27")
      (footprint "eagle-import:B1,27")
      (libsource (lib "eagle-import") (part "PTR1B1,27"))
    )
    (comp (ref "U1")
      (value "ATMEGA4809")
      (footprint "eagle-import:TQFP48")
      (fields (field (name "MANUFACTURER") "Microchip") (field (name "MPN") "ATMEGA4809-AFR"))
      (libsource (lib "eagle-import") (part "ATMEGA4809"))
    )
    (comp (ref "U2")
      (value "CH340E_MSOP10")
      (footprint "eagle-import:MSOP10")
      (fields (field (name "MF") "Jiangsu Qin Heng") (field (name "MPN") "CH340E"))
      (libsource (lib "eagle-import") (part "CH340E_MSOP10"))
    )
  )
  (nets
    (net (code "1") (name "+5V") (class "Default")
      (node (ref "C11") (pin "1") (pinfunction "1_1") (pintype "passive"))
      (node (ref "C12") (pin "1") (pinfunction "1_1") (pintype "passive"))
      (node (ref "C13") (pin "1") (pinfunction "1_1") (pintype "passive"))
      (node (ref "C14") (pin "1") (pinfunction "1_1") (pintype "passive"))
      (node (ref "C15") (pin "1") (pinfunction "1_1") (pintype "passive"))
      (node (ref "C16") (pin "1") (pinfunction "1_1") (pintype "passive"))
      (node (ref "C19") (pin "1") (pinfunction "1_1") (pintype "passive"))
      (node (ref "C20") (pin "1") (pinfunction "1_1") (pintype "passive"))
      (node (ref "C9") (pin "1") (pinfunction "1_1") (pintype "passive"))
      (node (ref "D1") (pin "3") (pinfunction "4_3") (pintype "passive"))
      (node (ref "D12") (pin "C") (pinfunction "C_C") (pintype "passive"))
      (node (ref "D13") (pin "C") (pinfunction "C_C") (pintype "passive"))
      (node (ref "D2") (pin "1") (pinfunction "VDD_1") (pintype "power_in"))
      (node (ref "DEBUG") (pin "4") (pinfunction "VTG_4") (pintype "power_in"))
      (node (ref "J1") (pin "2") (pinfunction "VCC_2") (pintype "power_in"))
      (node (ref "J2") (pin "2") (pinfunction "VCC_2") (pintype "power_in"))
      (node (ref "JP6") (pin "1@1") (pinfunction "1_1@1") (pintype "passive"))
      (node (ref "JP6") (pin "1@2") (pinfunction "1_1@2") (pintype "passive"))
      (node (ref "JP6") (pin "1@3") (pinfunction "1_1@3") (pintype "passive"))
      (node (ref "JP6") (pin "1@4") (pinfunction "1_1@4") (pintype "passive"))
      (node (ref "JP6") (pin "1@5") (pinfunction "1_1@5") (pintype "passive"))
      (node (ref "JP6") (pin "1@6") (pinfunction "1_1@6") (pintype "passive"))
      (node (ref "LS1") (pin "+") (pinfunction "1_+") (pintype "passive"))
      (node (ref "LS2") (pin "+") (pinfunction "1_+") (pintype "passive"))
      (node (ref "LS3") (pin "+") (pinfunction "1_+") (pintype "passive"))
      (node (ref "LS4") (pin "+") (pinfunction "1_+") (pintype "passive"))
      (node (ref "LS5") (pin "+") (pinfunction "1_+") (pintype "passive"))
      (node (ref "LS6") (pin "+") (pinfunction "1_+") (pintype "passive"))
      (node (ref "LS7") (pin "+") (pinfunction "1_+") (pintype "passive"))
      (node (ref "LS8") (pin "+") (pinfunction "1_+") (pintype "passive"))
      (node (ref "R12") (pin "2") (pinfunction "2_2") (pintype "passive"))
      (node (ref "R14") (pin "2") (pinfunction "2_2") (pintype "passive"))
      (node (ref "R16") (pin "2") (pinfunction "2_2") (pintype "passive"))
      (node (ref "R18") (pin "2") (pinfunction "2_2") (pintype "passive"))
      (node (ref "R20") (pin "2") (pinfunction "2_2") (pintype "passive"))
      (node (ref "R22") (pin "2") (pinfunction "2_2") (pintype "passive"))
      (node (ref "R24") (pin "2") (pinfunction "2_2") (pintype "passive"))
      (node (ref "R26") (pin "2") (pinfunction "2_2") (pintype "passive"))
      (node (ref "R28") (pin "2") (pinfunction "2_2") (pintype "passive"))
      (node (ref "R29") (pin "2") (pinfunction "2_2") (pintype "passive"))
      (node (ref "R30") (pin "2") (pinfunction "2_2") (pintype "passive"))
      (node (ref "R31") (pin "2") (pinfunction "2_2") (pintype "passive"))
      (node (ref "R32") (pin "2") (pinfunction "2_2") (pintype "passive"))
      (node (ref "R33") (pin "2") (pinfunction "2_2") (pintype "passive"))
      (node (ref "R34") (pin "2") (pinfunction "2_2") (pintype "passive"))
      (node (ref "R35") (pin "2") (pinfunction "2_2") (pintype "passive"))
      (node (ref "R36") (pin "2") (pinfunction "2_2") (pintype "passive"))
      (node (ref "R37") (pin "2") (pinfunction "2_2") (pintype "passive"))
      (node (ref "R41") (pin "2") (pinfunction "2_2") (pintype "passive"))
      (node (ref "R44") (pin "1") (pinfunction "1_1") (pintype "passive"))
      (node (ref "U1") (pin "14") (pinfunction "VDD_14") (pintype "bidirectional"))
      (node (ref "U1") (pin "28") (pinfunction "AVDD_28") (pintype "bidirectional"))
      (node (ref "U1") (pin "42") (pinfunction "VDD_42") (pintype "bidirectional"))
      (node (ref "U2") (pin "7") (pinfunction "VCC_7") (pintype "power_in"))
    )
    (net (code "2") (name "/AVCC1") (class "Default")
      (node (ref "REFX3") (pin "F6") (pinfunction "AVCC1_F6") (pintype "power_in"))
    )
    (net (code "3") (name "/AVCC2") (class "Default")
      (node (ref "REFX3") (pin "D5") (pinfunction "AVCC2_D5") (pintype "power_in"))
    )
    (net (code "4") (name "/AVSS1") (class "Default")
      (node (ref "REFX3") (pin "F5") (pinfunction "AVSS1_F5") (pintype "power_in"))
    )
    (net (code "5") (name "/AVSS2") (class "Default")
      (node (ref "REFX3") (pin "D6") (pinfunction "AVSS2_D6") (pintype "power_in"))
    )
    (net (code "6") (name "/AVSS3") (class "Default")
      (node (ref "REFX3") (pin "E5") (pinfunction "AVSS3_E5") (pintype "power_in"))
    )
    (net (code "7") (name "/D13~{}") (class "Default")
      (node (ref "TP5") (pin "TP") (pinfunction "TP_TP") (pintype "input"))
      (node (ref "U1") (pin "9") (pinfunction "PB05_9") (pintype "bidirectional"))
    )
    (net (code "8") (name "/D14~{{slash}TX1}") (class "Default")
      (node (ref "R38") (pin "1") (pinfunction "1_1") (pintype "passive"))
      (node (ref "U1") (pin "10") (pinfunction "PC00_10") (pintype "bidirectional"))
    )
    (net (code "9") (name "/D15~{{slash}RX1}") (class "Default")
      (node (ref "R39") (pin "1") (pinfunction "1_1") (pintype "passive"))
      (node (ref "U1") (pin "11") (pinfunction "PC01_11") (pintype "bidirectional"))
    )
    (net (code "10") (name "/D16~{}") (class "Default")
      (node (ref "TP4") (pin "TP") (pinfunction "TP_TP") (pintype "input"))
      (node (ref "U1") (pin "12") (pinfunction "PC02_12") (pintype "bidirectional"))
    )
    (net (code "11") (name "/D17~{}") (class "Default")
      (node (ref "TP3") (pin "TP") (pinfunction "TP_TP") (pintype "input"))
      (node (ref "U1") (pin "13") (pinfunction "PC03_13") (pintype "bidirectional"))
    )
    (net (code "12") (name "/D18~{}") (class "Default")
      (node (ref "JP4") (pin "1@1") (pinfunction "1_1@1") (pintype "passive"))
      (node (ref "JP4") (pin "1@2") (pinfunction "1_1@2") (pintype "passive"))
      (node (ref "JP4") (pin "1@3") (pinfunction "1_1@3") (pintype "passive"))
      (node (ref "JP4") (pin "1@4") (pinfunction "1_1@4") (pintype "passive"))
      (node (ref "JP4") (pin "1@5") (pinfunction "1_1@5") (pintype "passive"))
      (node (ref "JP4") (pin "1@6") (pinfunction "1_1@6") (pintype "passive"))
      (node (ref "U1") (pin "16") (pinfunction "PC04_16") (pintype "bidirectional"))
    )
    (net (code "13") (name "/D19~{}") (class "Default")
      (node (ref "U1") (pin "17") (pinfunction "PC05_17") (pintype "bidirectional"))
    )
    (net (code "14") (name "/D38~{{slash}A14}") (class "Default")
      (node (ref "R2") (pin "1") (pinfunction "1_1") (pintype "passive"))
      (node (ref "U1") (pin "38") (pinfunction "PF04_38") (pintype "bidirectional"))
    )
    (net (code "15") (name "/D39~{{slash}A15}") (class "Default")
      (node (ref "R3") (pin "1") (pinfunction "1_1") (pintype "passive"))
      (node (ref "U1") (pin "39") (pinfunction "PF05_39") (pintype "bidirectional"))
    )
    (net (code "16") (name "/DCOR") (class "Default")
      (node (ref "REFX3") (pin "J8") (pinfunction "DCOR_J8") (pintype "power_in"))
    )
    (net (code "17") (name "/DVCC1") (class "Default")
      (node (ref "REFX3") (pin "D2") (pinfunction "DVCC1_D2") (pintype "power_in"))
    )
    (net (code "18") (name "/DVCC2") (class "Default")
      (node (ref "REFX3") (pin "C6") (pinfunction "DVCC2_C6") (pintype "power_in"))
    )
    (net (code "19") (name "/DVSS1") (class "Default")
      (node (ref "REFX3") (pin "F2") (pinfunction "DVSS1_F2") (pintype "power_in"))
    )
    (net (code "20") (name "/DVSS2") (class "Default")
      (node (ref "REFX3") (pin "E6") (pinfunction "DVSS2_E6") (pintype "power_in"))
    )
    (net (code "21") (name "/DVSS3") (class "Default")
      (node (ref "REFX3") (pin "C7") (pinfunction "DVSS3_C7") (pintype "power_in"))
    )
    (net (code "22") (name "/VCORE") (class "Default")
      (node (ref "REFX3") (pin "C2") (pinfunction "VCORE_C2") (pintype "power_in"))
    )
    (net (code "23") (name "/VSW") (class "Default")
      (node (ref "REFX3") (pin "E2") (pinfunction "VSW_E2") (pintype "power_in"))
    )
    (net (code "24") (name "D0") (class "Default")
      (node (ref "Q8") (pin "1") (pinfunction "G_1") (pintype "passive"))
      (node (ref "R11") (pin "2") (pinfunction "2_2") (pintype "passive"))
      (node (ref "U1") (pin "44") (pinfunction "(EXTCLK)PA00_44") (pintype "bidirectional"))
    )
    (net (code "25") (name "D1") (class "Default")
      (node (ref "Q7") (pin "1") (pinfunction "G_1") (pintype "passive"))
      (node (ref "R10") (pin "2") (pinfunction "2_2") (pintype "passive"))
      (node (ref "U1") (pin "45") (pinfunction "PA01_45") (pintype "bidirectional"))
    )
    (net (code "26") (name "D2{slash}SDA") (class "Default")
      (node (ref "J1") (pin "3") (pinfunction "SDA_3") (pintype "passive"))
      (node (ref "J2") (pin "3") (pinfunction "SDA_3") (pintype "passive"))
      (node (ref "R36") (pin "1") (pinfunction "1_1") (pintype "passive"))
      (node (ref "U1") (pin "46") (pinfunction "PA02_46") (pintype "bidirectional"))
    )
    (net (code "27") (name "D3{slash}SCL") (class "Default")
      (node (ref "J1") (pin "4") (pinfunction "SCL_4") (pintype "passive"))
      (node (ref "J2") (pin "4") (pinfunction "SCL_4") (pintype "passive"))
      (node (ref "R37") (pin "1") (pinfunction "1_1") (pintype "passive"))
      (node (ref "U1") (pin "47") (pinfunction "PA03_47") (pintype "bidirectional"))
    )
    (net (code "28") (name "D4") (class "Default")
      (node (ref "Q6") (pin "1") (pinfunction "G_1") (pintype "passive"))
      (node (ref "R9") (pin "2") (pinfunction "2_2") (pintype "passive"))
      (node (ref "U1") (pin "48") (pinfunction "PA04_48") (pintype "bidirectional"))
    )
    (net (code "29") (name "D5") (class "Default")
      (node (ref "Q5") (pin "1") (pinfunction "G_1") (pintype "passive"))
      (node (ref "R8") (pin "2") (pinfunction "2_2") (pintype "passive"))
      (node (ref "U1") (pin "1") (pinfunction "PA05_1") (pintype "bidirectional"))
    )
    (net (code "30") (name "D6") (class "Default")
      (node (ref "Q4") (pin "1") (pinfunction "G_1") (pintype "passive"))
      (node (ref "R7") (pin "2") (pinfunction "2_2") (pintype "passive"))
      (node (ref "U1") (pin "2") (pinfunction "PA06_2") (pintype "bidirectional"))
    )
    (net (code "31") (name "D7") (class "Default")
      (node (ref "Q3") (pin "1") (pinfunction "G_1") (pintype "passive"))
      (node (ref "R6") (pin "2") (pinfunction "2_2") (pintype "passive"))
      (node (ref "U1") (pin "3") (pinfunction "PA07_3") (pintype "bidirectional"))
    )
    (net (code "32") (name "D8") (class "Default")
      (node (ref "Q2") (pin "1") (pinfunction "G_1") (pintype "passive"))
      (node (ref "R5") (pin "2") (pinfunction "2_2") (pintype "passive"))
      (node (ref "U1") (pin "4") (pinfunction "PB00_4") (pintype "bidirectional"))
    )
    (net (code "33") (name "D9") (class "Default")
      (node (ref "Q1") (pin "1") (pinfunction "G_1") (pintype "passive"))
      (node (ref "R4") (pin "2") (pinfunction "2_2") (pintype "passive"))
      (node (ref "U1") (pin "5") (pinfunction "PB01_5") (pintype "bidirectional"))
    )
    (net (code "34") (name "D10") (class "Default")
      (node (ref "D2") (pin "4") (pinfunction "DIN_4") (pintype "input"))
      (node (ref "U1") (pin "6") (pinfunction "PB02_6") (pintype "bidirectional"))
    )
    (net (code "35") (name "D11") (class "Default")
      (node (ref "U1") (pin "7") (pinfunction "PB03_7") (pintype "bidirectional"))
    )
    (net (code "36") (name "D12") (class "Default")
      (node (ref "U1") (pin "8") (pinfunction "PB04_8") (pintype "bidirectional"))
    )
    (net (code "37") (name "D20") (class "Default")
      (node (ref "C1") (pin "1") (pinfunction "1_1") (pintype "passive"))
      (node (ref "S1") (pin "1") (pinfunction "P_1") (pintype "passive"))
      (node (ref "S1") (pin "2") (pinfunction "P_2") (pintype "passive"))
      (node (ref "U1") (pin "18") (pinfunction "PC06_18") (pintype "bidirectional"))
    )
    (net (code "38") (name "D21") (class "Default")
      (node (ref "C2") (pin "1") (pinfunction "1_1") (pintype "passive"))
      (node (ref "S2") (pin "1") (pinfunction "P_1") (pintype "passive"))
      (node (ref "S2") (pin "2") (pinfunction "P_2") (pintype "passive"))
      (node (ref "U1") (pin "19") (pinfunction "PC07_19") (pintype "bidirectional"))
    )
    (net (code "39") (name "D22{slash}A0") (class "Default")
      (node (ref "C3") (pin "1") (pinfunction "1_1") (pintype "passive"))
      (node (ref "S3") (pin "1") (pinfunction "P_1") (pintype "passive"))
      (node (ref "S3") (pin "2") (pinfunction "P_2") (pintype "passive"))
      (node (ref "U1") (pin "20") (pinfunction "PD00_20") (pintype "bidirectional"))
    )
    (net (code "40") (name "D23{slash}A1") (class "Default")
      (node (ref "JP3") (pin "1@1") (pinfunction "1_1@1") (pintype "passive"))
      (node (ref "JP3") (pin "1@2") (pinfunction "1_1@2") (pintype "passive"))
      (node (ref "JP3") (pin "1@3") (pinfunction "1_1@3") (pintype "passive"))
      (node (ref "JP3") (pin "1@4") (pinfunction "1_1@4") (pintype "passive"))
      (node (ref "JP3") (pin "1@5") (pinfunction "1_1@5") (pintype "passive"))
      (node (ref "JP3") (pin "1@6") (pinfunction "1_1@6") (pintype "passive"))
      (node (ref "U1") (pin "21") (pinfunction "PD01_21") (pintype "bidirectional"))
    )
    (net (code "41") (name "D24{slash}A2") (class "Default")
      (node (ref "JP2") (pin "1@1") (pinfunction "1_1@1") (pintype "passive"))
      (node (ref "JP2") (pin "1@2") (pinfunction "1_1@2") (pintype "passive"))
      (node (ref "JP2") (pin "1@3") (pinfunction "1_1@3") (pintype "passive"))
      (node (ref "JP2") (pin "1@4") (pinfunction "1_1@4") (pintype "passive"))
      (node (ref "JP2") (pin "1@5") (pinfunction "1_1@5") (pintype "passive"))
      (node (ref "JP2") (pin "1@6") (pinfunction "1_1@6") (pintype "passive"))
      (node (ref "U1") (pin "22") (pinfunction "PD02_22") (pintype "bidirectional"))
    )
    (net (code "42") (name "D25{slash}A3") (class "Default")
      (node (ref "JP1") (pin "1@1") (pinfunction "1_1@1") (pintype "passive"))
      (node (ref "JP1") (pin "1@2") (pinfunction "1_1@2") (pintype "passive"))
      (node (ref "JP1") (pin "1@3") (pinfunction "1_1@3") (pintype "passive"))
      (node (ref "JP1") (pin "1@4") (pinfunction "1_1@4") (pintype "passive"))
      (node (ref "JP1") (pin "1@5") (pinfunction "1_1@5") (pintype "passive"))
      (node (ref "JP1") (pin "1@6") (pinfunction "1_1@6") (pintype "passive"))
      (node (ref "U1") (pin "23") (pinfunction "PD03_23") (pintype "bidirectional"))
    )
    (net (code "43") (name "D26{slash}A4") (class "Default")
      (node (ref "TP1") (pin "TP") (pinfunction "TP_TP") (pintype "input"))
      (node (ref "U1") (pin "24") (pinfunction "PD04_24") (pintype "bidirectional"))
    )
    (net (code "44") (name "D27{slash}A5") (class "Default")
      (node (ref "TP2") (pin "TP") (pinfunction "TP_TP") (pintype "input"))
      (node (ref "U1") (pin "25") (pinfunction "PD05_25") (pintype "bidirectional"))
    )
    (net (code "45") (name "D28{slash}A6") (class "Default")
      (node (ref "U1") (pin "26") (pinfunction "PD06_26") (pintype "bidirectional"))
    )
    (net (code "46") (name "D29{slash}A7{slash}AREF") (class "Default")
      (node (ref "U1") (pin "27") (pinfunction "PD07_27") (pintype "bidirectional"))
    )
    (net (code "47") (name "D30{slash}A8") (class "Default")
      (node (ref "C10") (pin "1") (pinfunction "1_1") (pintype "passive"))
      (node (ref "S9") (pin "1") (pinfunction "P_1") (pintype "passive"))
      (node (ref "S9") (pin "2") (pinfunction "P_2") (pintype "passive"))
      (node (ref "U1") (pin "30") (pinfunction "PE00_30") (pintype "bidirectional"))
    )
    (net (code "48") (name "D31{slash}A9") (class "Default")
      (node (ref "U1") (pin "31") (pinfunction "PE01_31") (pintype "bidirectional"))
    )
    (net (code "49") (name "D32{slash}A10") (class "Default")
      (node (ref "C4") (pin "1") (pinfunction "1_1") (pintype "passive"))
      (node (ref "S4") (pin "1") (pinfunction "P_1") (pintype "passive"))
      (node (ref "S4") (pin "2") (pinfunction "P_2") (pintype "passive"))
      (node (ref "U1") (pin "32") (pinfunction "PE02_32") (pintype "bidirectional"))
    )
    (net (code "50") (name "D33{slash}A11") (class "Default")
      (node (ref "C5") (pin "1") (pinfunction "1_1") (pintype "passive"))
      (node (ref "S5") (pin "1") (pinfunction "P_1") (pintype "passive"))
      (node (ref "S5") (pin "2") (pinfunction "P_2") (pintype "passive"))
      (node (ref "U1") (pin "33") (pinfunction "PE03_33") (pintype "bidirectional"))
    )
    (net (code "51") (name "D34") (class "Default")
      (node (ref "C6") (pin "1") (pinfunction "1_1") (pintype "passive"))
      (node (ref "S6") (pin "1") (pinfunction "P_1") (pintype "passive"))
      (node (ref "S6") (pin "2") (pinfunction "P_2") (pintype "passive"))
      (node (ref "U1") (pin "34") (pinfunction "PF00_34") (pintype "bidirectional"))
    )
    (net (code "52") (name "D35") (class "Default")
      (node (ref "C7") (pin "1") (pinfunction "1_1") (pintype "passive"))
      (node (ref "S7") (pin "1") (pinfunction "P_1") (pintype "passive"))
      (node (ref "S7") (pin "2") (pinfunction "P_2") (pintype "passive"))
      (node (ref "U1") (pin "35") (pinfunction "PF01_35") (pintype "bidirectional"))
    )
    (net (code "53") (name "D36{slash}A12") (class "Default")
      (node (ref "C8") (pin "1") (pinfunction "1_1") (pintype "passive"))
      (node (ref "S8") (pin "1") (pinfunction "P_1") (pintype "passive"))
      (node (ref "S8") (pin "2") (pinfunction "P_2") (pintype "passive"))
      (node (ref "U1") (pin "36") (pinfunction "PF02_36") (pintype "bidirectional"))
    )
    (net (code "54") (name "D37{slash}A13") (class "Default")
      (node (ref "R1") (pin "1") (pinfunction "1_1") (pintype "passive"))
      (node (ref "U1") (pin "37") (pinfunction "PF03_37") (pintype "bidirectional"))
    )
    (net (code "55") (name "GND") (class "Default")
      (node (ref "C1") (pin "2") (pinfunction "2_2") (pintype "passive"))
      (node (ref "C10") (pin "2") (pinfunction "2_2") (pintype "passive"))
      (node (ref "C11") (pin "2") (pinfunction "2_2") (pintype "passive"))
      (node (ref "C12") (pin "2") (pinfunction "2_2") (pintype "passive"))
      (node (ref "C13") (pin "2") (pinfunction "2_2") (pintype "passive"))
      (node (ref "C14") (pin "2") (pinfunction "2_2") (pintype "passive"))
      (node (ref "C15") (pin "2") (pinfunction "2_2") (pintype "passive"))
      (node (ref "C16") (pin "2") (pinfunction "2_2") (pintype "passive"))
      (node (ref "C18") (pin "2") (pinfunction "2_2") (pintype "passive"))
      (node (ref "C19") (pin "2") (pinfunction "2_2") (pintype "passive"))
      (node (ref "C2") (pin "2") (pinfunction "2_2") (pintype "passive"))
      (node (ref "C20") (pin "2") (pinfunction "2_2") (pintype "passive"))
      (node (ref "C3") (pin "2") (pinfunction "2_2") (pintype "passive"))
      (node (ref "C4") (pin "2") (pinfunction "2_2") (pintype "passive"))
      (node (ref "C5") (pin "2") (pinfunction "2_2") (pintype "passive"))
      (node (ref "C6") (pin "2") (pinfunction "2_2") (pintype "passive"))
      (node (ref "C7") (pin "2") (pinfunction "2_2") (pintype "passive"))
      (node (ref "C8") (pin "2") (pinfunction "2_2") (pintype "passive"))
      (node (ref "C9") (pin "2") (pinfunction "2_2") (pintype "passive"))
      (node (ref "D11") (pin "C") (pinfunction "C_C") (pintype "passive"))
      (node (ref "D14") (pin "C") (pinfunction "C_C") (pintype "passive"))
      (node (ref "D2") (pin "3") (pinfunction "VSS_3") (pintype "power_in"))
      (node (ref "DEBUG") (pin "2") (pinfunction "GND_2") (pintype "power_in"))
      (node (ref "J1") (pin "1") (pinfunction "GND_1") (pintype "power_in"))
      (node (ref "J2") (pin "1") (pinfunction "GND_1") (pintype "power_in"))
      (node (ref "J3") (pin "1") (pinfunction "1_1") (pintype "passive"))
      (node (ref "J4") (pin "GND") (pinfunction "GND_GND") (pintype "power_in"))
      (node (ref "J4") (pin "GND2") (pinfunction "GND_GND2") (pintype "power_in"))
      (node (ref "J4") (pin "SHLD1") (pinfunction "SHLD_SHLD1") (pintype "passive"))
      (node (ref "J4") (pin "SHLD2") (pinfunction "SHLD_SHLD2") (pintype "passive"))
      (node (ref "J4") (pin "SHLD3") (pinfunction "SHLD_SHLD3") (pintype "passive"))
      (node (ref "J4") (pin "SHLD4") (pinfunction "SHLD_SHLD4") (pintype "passive"))
      (node (ref "J4") (pin "SHLD5") (pinfunction "SHLD_SHLD5") (pintype "passive"))
      (node (ref "J4") (pin "SHLD6") (pinfunction "SHLD_SHLD6") (pintype "passive"))
      (node (ref "J4") (pin "SHLD7") (pinfunction "SHLD_SHLD7") (pintype "passive"))
      (node (ref "J4") (pin "SHLD8") (pinfunction "SHLD_SHLD8") (pintype "passive"))
      (node (ref "JP5") (pin "1@1") (pinfunction "1_1@1") (pintype "passive"))
      (node (ref "JP5") (pin "1@2") (pinfunction "1_1@2") (pintype "passive"))
      (node (ref "JP5") (pin "1@3") (pinfunction "1_1@3") (pintype "passive"))
      (node (ref "JP5") (pin "1@4") (pinfunction "1_1@4") (pintype "passive"))
      (node (ref "JP5") (pin "1@5") (pinfunction "1_1@5") (pintype "passive"))
      (node (ref "JP5") (pin "1@6") (pinfunction "1_1@6") (pintype "passive"))
      (node (ref "Q1") (pin "2") (pinfunction "S_2") (pintype "passive"))
      (node (ref "Q2") (pin "2") (pinfunction "S_2") (pintype "passive"))
      (node (ref "Q3") (pin "2") (pinfunction "S_2") (pintype "passive"))
      (node (ref "Q4") (pin "2") (pinfunction "S_2") (pintype "passive"))
      (node (ref "Q5") (pin "2") (pinfunction "S_2") (pintype "passive"))
      (node (ref "Q6") (pin "2") (pinfunction "S_2") (pintype "passive"))
      (node (ref "Q7") (pin "2") (pinfunction "S_2") (pintype "passive"))
      (node (ref "Q8") (pin "2") (pinfunction "S_2") (pintype "passive"))
      (node (ref "R10") (pin "1") (pinfunction "1_1") (pintype "passive"))
      (node (ref "R11") (pin "1") (pinfunction "1_1") (pintype "passive"))
      (node (ref "R4") (pin "1") (pinfunction "1_1") (pintype "passive"))
      (node (ref "R42") (pin "1") (pinfunction "1_1") (pintype "passive"))
      (node (ref "R43") (pin "1") (pinfunction "1_1") (pintype "passive"))
      (node (ref "R5") (pin "1") (pinfunction "1_1") (pintype "passive"))
      (node (ref "R6") (pin "1") (pinfunction "1_1") (pintype "passive"))
      (node (ref "R7") (pin "1") (pinfunction "1_1") (pintype "passive"))
      (node (ref "R8") (pin "1") (pinfunction "1_1") (pintype "passive"))
      (node (ref "R9") (pin "1") (pinfunction "1_1") (pintype "passive"))
      (node (ref "S1") (pin "3") (pinfunction "S_3") (pintype "passive"))
      (node (ref "S1") (pin "4") (pinfunction "S_4") (pintype "passive"))
      (node (ref "S2") (pin "3") (pinfunction "S_3") (pintype "passive"))
      (node (ref "S2") (pin "4") (pinfunction "S_4") (pintype "passive"))
      (node (ref "S3") (pin "3") (pinfunction "S_3") (pintype "passive"))
      (node (ref "S3") (pin "4") (pinfunction "S_4") (pintype "passive"))
      (node (ref "S4") (pin "3") (pinfunction "S_3") (pintype "passive"))
      (node (ref "S4") (pin "4") (pinfunction "S_4") (pintype "passive"))
      (node (ref "S5") (pin "3") (pinfunction "S_3") (pintype "passive"))
      (node (ref "S5") (pin "4") (pinfunction "S_4") (pintype "passive"))
      (node (ref "S6") (pin "3") (pinfunction "S_3") (pintype "passive"))
      (node (ref "S6") (pin "4") (pinfunction "S_4") (pintype "passive"))
      (node (ref "S7") (pin "3") (pinfunction "S_3") (pintype "passive"))
      (node (ref "S7") (pin "4") (pinfunction "S_4") (pintype "passive"))
      (node (ref "S8") (pin "3") (pinfunction "S_3") (pintype "passive"))
      (node (ref "S8") (pin "4") (pinfunction "S_4") (pintype "passive"))
      (node (ref "S9") (pin "3") (pinfunction "S_3") (pintype "passive"))
      (node (ref "S9") (pin "4") (pinfunction "S_4") (pintype "passive"))
      (node (ref "U1") (pin "15") (pinfunction "GND_15") (pintype "bidirectional"))
      (node (ref "U1") (pin "29") (pinfunction "GND_29") (pintype "bidirectional"))
      (node (ref "U1") (pin "43") (pinfunction "GND_43") (pintype "bidirectional"))
      (node (ref "U2") (pin "3") (pinfunction "GND_3") (pintype "bidirectional"))
    )
    (net (code "56") (name "Net-(D1-B)") (class "Default")
      (node (ref "D1") (pin "2") (pinfunction "B_2") (pintype "passive"))
      (node (ref "R1") (pin "2") (pinfunction "2_2") (pintype "passive"))
    )
    (net (code "57") (name "Net-(D1-G)") (class "Default")
      (node (ref "D1") (pin "1") (pinfunction "G_1") (pintype "passive"))
      (node (ref "R3") (pin "2") (pinfunction "2_2") (pintype "passive"))
    )
    (net (code "58") (name "Net-(D1-R)") (class "Default")
      (node (ref "D1") (pin "4") (pinfunction "R_4") (pintype "passive"))
      (node (ref "R2") (pin "2") (pinfunction "2_2") (pintype "passive"))
    )
    (net (code "59") (name "Net-(D3-PadA)") (class "Default")
      (node (ref "D3") (pin "A") (pinfunction "A_A") (pintype "passive"))
      (node (ref "R28") (pin "1") (pinfunction "1_1") (pintype "passive"))
    )
    (net (code "60") (name "Net-(D4-PadA)") (class "Default")
      (node (ref "D4") (pin "A") (pinfunction "A_A") (pintype "passive"))
      (node (ref "R29") (pin "1") (pinfunction "1_1") (pintype "passive"))
    )
    (net (code "61") (name "Net-(D5-PadA)") (class "Default")
      (node (ref "D5") (pin "A") (pinfunction "A_A") (pintype "passive"))
      (node (ref "R30") (pin "1") (pinfunction "1_1") (pintype "passive"))
    )
    (net (code "62") (name "Net-(D6-PadA)") (class "Default")
      (node (ref "D6") (pin "A") (pinfunction "A_A") (pintype "passive"))
      (node (ref "R31") (pin "1") (pinfunction "1_1") (pintype "passive"))
    )
    (net (code "63") (name "Net-(D7-PadA)") (class "Default")
      (node (ref "D7") (pin "A") (pinfunction "A_A") (pintype "passive"))
      (node (ref "R32") (pin "1") (pinfunction "1_1") (pintype "passive"))
    )
    (net (code "64") (name "Net-(D8-PadA)") (class "Default")
      (node (ref "D8") (pin "A") (pinfunction "A_A") (pintype "passive"))
      (node (ref "R33") (pin "1") (pinfunction "1_1") (pintype "passive"))
    )
    (net (code "65") (name "Net-(D9-PadA)") (class "Default")
      (node (ref "D9") (pin "A") (pinfunction "A_A") (pintype "passive"))
      (node (ref "R34") (pin "1") (pinfunction "1_1") (pintype "passive"))
    )
    (net (code "66") (name "Net-(D10-PadA)") (class "Default")
      (node (ref "D10") (pin "A") (pinfunction "A_A") (pintype "passive"))
      (node (ref "R35") (pin "1") (pinfunction "1_1") (pintype "passive"))
    )
    (net (code "67") (name "Net-(D11-PadA)") (class "Default")
      (node (ref "D11") (pin "A") (pinfunction "A_A") (pintype "passive"))
      (node (ref "R40") (pin "2") (pinfunction "2_2") (pintype "passive"))
    )
    (net (code "68") (name "Net-(D14-PadA)") (class "Default")
      (node (ref "D14") (pin "A") (pinfunction "A_A") (pintype "passive"))
      (node (ref "R44") (pin "2") (pinfunction "2_2") (pintype "passive"))
    )
    (net (code "69") (name "Net-(J4-CC1)") (class "Default")
      (node (ref "J4") (pin "A5") (pinfunction "CC1_A5") (pintype "passive"))
      (node (ref "R43") (pin "2") (pinfunction "2_2") (pintype "passive"))
    )
    (net (code "70") (name "Net-(J4-CC2)") (class "Default")
      (node (ref "J4") (pin "B5") (pinfunction "CC2_B5") (pintype "passive"))
      (node (ref "R42") (pin "2") (pinfunction "2_2") (pintype "passive"))
    )
    (net (code "71") (name "Net-(LS1-2)") (class "Default")
      (node (ref "LS1") (pin "-") (pinfunction "2_-") (pintype "passive"))
      (node (ref "R18") (pin "1") (pinfunction "1_1") (pintype "passive"))
      (node (ref "R19") (pin "2") (pinfunction "2_2") (pintype "passive"))
    )
    (net (code "72") (name "Net-(LS2-2)") (class "Default")
      (node (ref "LS2") (pin "-") (pinfunction "2_-") (pintype "passive"))
      (node (ref "R14") (pin "1") (pinfunction "1_1") (pintype "passive"))
      (node (ref "R15") (pin "2") (pinfunction "2_2") (pintype "passive"))
    )
    (net (code "73") (name "Net-(LS3-2)") (class "Default")
      (node (ref "LS3") (pin "-") (pinfunction "2_-") (pintype "passive"))
      (node (ref "R24") (pin "1") (pinfunction "1_1") (pintype "passive"))
      (node (ref "R25") (pin "2") (pinfunction "2_2") (pintype "passive"))
    )
    (net (code "74") (name "Net-(LS4-2)") (class "Default")
      (node (ref "LS4") (pin "-") (pinfunction "2_-") (pintype "passive"))
      (node (ref "R20") (pin "1") (pinfunction "1_1") (pintype "passive"))
      (node (ref "R21") (pin "2") (pinfunction "2_2") (pintype "passive"))
    )
    (net (code "75") (name "Net-(LS5-2)") (class "Default")
      (node (ref "LS5") (pin "-") (pinfunction "2_-") (pintype "passive"))
      (node (ref "R12") (pin "1") (pinfunction "1_1") (pintype "passive"))
      (node (ref "R13") (pin "2") (pinfunction "2_2") (pintype "passive"))
    )
    (net (code "76") (name "Net-(LS6-2)") (class "Default")
      (node (ref "LS6") (pin "-") (pinfunction "2_-") (pintype "passive"))
      (node (ref "R26") (pin "1") (pinfunction "1_1") (pintype "passive"))
      (node (ref "R27") (pin "2") (pinfunction "2_2") (pintype "passive"))
    )
    (net (code "77") (name "Net-(LS7-2)") (class "Default")
      (node (ref "LS7") (pin "-") (pinfunction "2_-") (pintype "passive"))
      (node (ref "R16") (pin "1") (pinfunction "1_1") (pintype "passive"))
      (node (ref "R17") (pin "2") (pinfunction "2_2") (pintype "passive"))
    )
    (net (code "78") (name "Net-(LS8-2)") (class "Default")
      (node (ref "LS8") (pin "-") (pinfunction "2_-") (pintype "passive"))
      (node (ref "R22") (pin "1") (pinfunction "1_1") (pintype "passive"))
      (node (ref "R23") (pin "2") (pinfunction "2_2") (pintype "passive"))
    )
    (net (code "79") (name "Net-(Q1-D)") (class "Default")
      (node (ref "D3") (pin "C") (pinfunction "C_C") (pintype "passive"))
      (node (ref "Q1") (pin "3") (pinfunction "D_3") (pintype "passive"))
      (node (ref "R13") (pin "1") (pinfunction "1_1") (pintype "passive"))
    )
    (net (code "80") (name "Net-(Q2-D)") (class "Default")
      (node (ref "D4") (pin "C") (pinfunction "C_C") (pintype "passive"))
      (node (ref "Q2") (pin "3") (pinfunction "D_3") (pintype "passive"))
      (node (ref "R15") (pin "1") (pinfunction "1_1") (pintype "passive"))
    )
    (net (code "81") (name "Net-(Q3-D)") (class "Default")
      (node (ref "D5") (pin "C") (pinfunction "C_C") (pintype "passive"))
      (node (ref "Q3") (pin "3") (pinfunction "D_3") (pintype "passive"))
      (node (ref "R17") (pin "1") (pinfunction "1_1") (pintype "passive"))
    )
    (net (code "82") (name "Net-(Q4-D)") (class "Default")
      (node (ref "D6") (pin "C") (pinfunction "C_C") (pintype "passive"))
      (node (ref "Q4") (pin "3") (pinfunction "D_3") (pintype "passive"))
      (node (ref "R19") (pin "1") (pinfunction "1_1") (pintype "passive"))
    )
    (net (code "83") (name "Net-(Q5-D)") (class "Default")
      (node (ref "D7") (pin "C") (pinfunction "C_C") (pintype "passive"))
      (node (ref "Q5") (pin "3") (pinfunction "D_3") (pintype "passive"))
      (node (ref "R21") (pin "1") (pinfunction "1_1") (pintype "passive"))
    )
    (net (code "84") (name "Net-(Q6-D)") (class "Default")
      (node (ref "D8") (pin "C") (pinfunction "C_C") (pintype "passive"))
      (node (ref "Q6") (pin "3") (pinfunction "D_3") (pintype "passive"))
      (node (ref "R23") (pin "1") (pinfunction "1_1") (pintype "passive"))
    )
    (net (code "85") (name "Net-(Q7-D)") (class "Default")
      (node (ref "D9") (pin "C") (pinfunction "C_C") (pintype "passive"))
      (node (ref "Q7") (pin "3") (pinfunction "D_3") (pintype "passive"))
      (node (ref "R25") (pin "1") (pinfunction "1_1") (pintype "passive"))
    )
    (net (code "86") (name "Net-(Q8-D)") (class "Default")
      (node (ref "D10") (pin "C") (pinfunction "C_C") (pintype "passive"))
      (node (ref "Q8") (pin "3") (pinfunction "D_3") (pintype "passive"))
      (node (ref "R27") (pin "1") (pinfunction "1_1") (pintype "passive"))
    )
    (net (code "87") (name "Net-(U2-TNOW)") (class "Default")
      (node (ref "R40") (pin "1") (pinfunction "1_1") (pintype "passive"))
      (node (ref "U2") (pin "6") (pinfunction "TNOW_6") (pintype "output"))
    )
    (net (code "88") (name "Net-(U2-UD+)") (class "Default")
      (node (ref "J4") (pin "A6") (pinfunction "D+_A6") (pintype "bidirectional"))
      (node (ref "J4") (pin "B6") (pinfunction "D+_B6") (pintype "bidirectional"))
      (node (ref "U2") (pin "1") (pinfunction "UD+_1") (pintype "bidirectional"))
    )
    (net (code "89") (name "Net-(U2-UD-)") (class "Default")
      (node (ref "J4") (pin "A7") (pinfunction "D-_A7") (pintype "bidirectional"))
      (node (ref "J4") (pin "B7") (pinfunction "D-_B7") (pintype "bidirectional"))
      (node (ref "U2") (pin "2") (pinfunction "UD-_2") (pintype "bidirectional"))
    )
    (net (code "90") (name "Net-(U2-~{RTS})") (class "Default")
      (node (ref "C17") (pin "1") (pinfunction "1_1") (pintype "passive"))
      (node (ref "U2") (pin "4") (pinfunction "~{RTS}_4") (pintype "output"))
    )
    (net (code "91") (name "RESETN") (class "Default")
      (node (ref "C17") (pin "2") (pinfunction "2_2") (pintype "passive"))
      (node (ref "D12") (pin "A") (pinfunction "A_A") (pintype "passive"))
      (node (ref "R41") (pin "1") (pinfunction "1_1") (pintype "passive"))
      (node (ref "U1") (pin "40") (pinfunction "RST/PF06_40") (pintype "bidirectional"))
    )
    (net (code "92") (name "RXD") (class "Default")
      (node (ref "R38") (pin "2") (pinfunction "2_2") (pintype "passive"))
      (node (ref "U2") (pin "9") (pinfunction "RXD_9") (pintype "input"))
    )
    (net (code "93") (name "TXD") (class "Default")
      (node (ref "R39") (pin "2") (pinfunction "2_2") (pintype "passive"))
      (node (ref "U2") (pin "8") (pinfunction "TXD_8") (pintype "output"))
    )
    (net (code "94") (name "UPDI") (class "Default")
      (node (ref "DEBUG") (pin "3") (pinfunction "UDPI_3") (pintype "bidirectional"))
      (node (ref "U1") (pin "41") (pinfunction "UPDI_41") (pintype "bidirectional"))
    )
    (net (code "95") (name "V3") (class "Default")
      (node (ref "C18") (pin "1") (pinfunction "1_1") (pintype "passive"))
      (node (ref "U2") (pin "10") (pinfunction "V3_10") (pintype "passive"))
    )
    (net (code "96") (name "VBUS") (class "Default")
      (node (ref "D13") (pin "A") (pinfunction "A_A") (pintype "passive"))
      (node (ref "J3") (pin "2") (pinfunction "2_2") (pintype "passive"))
      (node (ref "J4") (pin "VBUS1") (pinfunction "VBUS_VBUS1") (pintype "power_in"))
      (node (ref "J4") (pin "VBUS2") (pinfunction "VBUS_VBUS2") (pintype "power_in"))
    )
    (net (code "97") (name "unconnected-(D2-DOUT-Pad2)") (class "Default")
      (node (ref "D2") (pin "2") (pinfunction "DOUT_2") (pintype "output"))
    )
    (net (code "98") (name "unconnected-(DEBUG-NSRST-Pad6)") (class "Default")
      (node (ref "DEBUG") (pin "6") (pinfunction "NSRST_6") (pintype "input"))
    )
    (net (code "99") (name "unconnected-(DEBUG-TCK-Pad1)") (class "Default")
      (node (ref "DEBUG") (pin "1") (pinfunction "TCK_1") (pintype "no_connect"))
    )
    (net (code "100") (name "unconnected-(DEBUG-TMS-Pad5)") (class "Default")
      (node (ref "DEBUG") (pin "5") (pinfunction "TMS_5") (pintype "no_connect"))
    )
    (net (code "101") (name "unconnected-(REFX1-Pad1)") (class "Default")
      (node (ref "REFX1") (pin "1") (pinfunction "1_1") (pintype "passive"))
    )
    (net (code "102") (name "unconnected-(REFX1-Pad2)") (class "Default")
      (node (ref "REFX1") (pin "2") (pinfunction "2_2") (pintype "passive"))
    )
    (net (code "103") (name "unconnected-(REFX2-Pad1)") (class "Default")
      (node (ref "REFX2") (pin "1") (pinfunction "1_1") (pintype "passive"))
    )
    (net (code "104") (name "unconnected-(REFX2-Pad2)") (class "Default")
      (node (ref "REFX2") (pin "2") (pinfunction "2_2") (pintype "passive"))
    )
    (net (code "105") (name "unconnected-(REFX3-P1.0-PadA1)") (class "Default")
      (node (ref "REFX3") (pin "A1") (pinfunction "P1.0_A1") (pintype "bidirectional"))
    )
    (net (code "106") (name "unconnected-(REFX3-P1.1-PadB1)") (class "Default")
      (node (ref "REFX3") (pin "B1") (pinfunction "P1.1_B1") (pintype "bidirectional"))
    )
    (net (code "107") (name "unconnected-(REFX3-P1.2-PadC4)") (class "Default")
      (node (ref "REFX3") (pin "C4") (pinfunction "P1.2_C4") (pintype "bidirectional"))
    )
    (net (code "108") (name "unconnected-(REFX3-P1.3-PadD4)") (class "Default")
      (node (ref "REFX3") (pin "D4") (pinfunction "P1.3_D4") (pintype "bidirectional"))
    )
    (net (code "109") (name "unconnected-(REFX3-P1.4-PadD3)") (class "Default")
      (node (ref "REFX3") (pin "D3") (pinfunction "P1.4_D3") (pintype "bidirectional"))
    )
    (net (code "110") (name "unconnected-(REFX3-P1.5-PadC1)") (class "Default")
      (node (ref "REFX3") (pin "C1") (pinfunction "P1.5_C1") (pintype "bidirectional"))
    )
    (net (code "111") (name "unconnected-(REFX3-P1.6-PadD1)") (class "Default")
      (node (ref "REFX3") (pin "D1") (pinfunction "P1.6_D1") (pintype "bidirectional"))
    )
    (net (code "112") (name "unconnected-(REFX3-P1.7-PadE1)") (class "Default")
      (node (ref "REFX3") (pin "E1") (pinfunction "P1.7_E1") (pintype "bidirectional"))
    )
    (net (code "113") (name "unconnected-(REFX3-P2.0-PadE4)") (class "Default")
      (node (ref "REFX3") (pin "E4") (pinfunction "P2.0_E4") (pintype "bidirectional"))
    )
    (net (code "114") (name "unconnected-(REFX3-P2.1-PadF1)") (class "Default")
      (node (ref "REFX3") (pin "F1") (pinfunction "P2.1_F1") (pintype "bidirectional"))
    )
    (net (code "115") (name "unconnected-(REFX3-P2.2-PadE3)") (class "Default")
      (node (ref "REFX3") (pin "E3") (pinfunction "P2.2_E3") (pintype "bidirectional"))
    )
    (net (code "116") (name "unconnected-(REFX3-P2.3-PadF4)") (class "Default")
      (node (ref "REFX3") (pin "F4") (pinfunction "P2.3_F4") (pintype "bidirectional"))
    )
    (net (code "117") (name "unconnected-(REFX3-P2.4-PadF3)") (class "Default")
      (node (ref "REFX3") (pin "F3") (pinfunction "P2.4_F3") (pintype "bidirectional"))
    )
    (net (code "118") (name "unconnected-(REFX3-P2.5-PadG1)") (class "Default")
      (node (ref "REFX3") (pin "G1") (pinfunction "P2.5_G1") (pintype "bidirectional"))
    )
    (net (code "119") (name "unconnected-(REFX3-P2.6-PadG2)") (class "Default")
      (node (ref "REFX3") (pin "G2") (pinfunction "P2.6_G2") (pintype "bidirectional"))
    )
    (net (code "120") (name "unconnected-(REFX3-P2.7-PadH1)") (class "Default")
      (node (ref "REFX3") (pin "H1") (pinfunction "P2.7_H1") (pintype "bidirectional"))
    )
    (net (code "121") (name "unconnected-(REFX3-P3.0-PadJ3)") (class "Default")
      (node (ref "REFX3") (pin "J3") (pinfunction "P3.0_J3") (pintype "bidirectional"))
    )
    (net (code "122") (name "unconnected-(REFX3-P3.1-PadH4)") (class "Default")
      (node (ref "REFX3") (pin "H4") (pinfunction "P3.1_H4") (pintype "bidirectional"))
    )
    (net (code "123") (name "unconnected-(REFX3-P3.2-PadG5)") (class "Default")
      (node (ref "REFX3") (pin "G5") (pinfunction "P3.2_G5") (pintype "bidirectional"))
    )
    (net (code "124") (name "unconnected-(REFX3-P3.3-PadJ4)") (class "Default")
      (node (ref "REFX3") (pin "J4") (pinfunction "P3.3_J4") (pintype "bidirectional"))
    )
    (net (code "125") (name "unconnected-(REFX3-P3.4-PadH5)") (class "Default")
      (node (ref "REFX3") (pin "H5") (pinfunction "P3.4_H5") (pintype "bidirectional"))
    )
    (net (code "126") (name "unconnected-(REFX3-P3.5-PadG6)") (class "Default")
      (node (ref "REFX3") (pin "G6") (pinfunction "P3.5_G6") (pintype "bidirectional"))
    )
    (net (code "127") (name "unconnected-(REFX3-P3.6-PadJ5)") (class "Default")
      (node (ref "REFX3") (pin "J5") (pinfunction "P3.6_J5") (pintype "bidirectional"))
    )
    (net (code "128") (name "unconnected-(REFX3-P3.7-PadH6)") (class "Default")
      (node (ref "REFX3") (pin "H6") (pinfunction "P3.7_H6") (pintype "bidirectional"))
    )
    (net (code "129") (name "unconnected-(REFX3-P4.0-PadH9)") (class "Default")
      (node (ref "REFX3") (pin "H9") (pinfunction "P4.0_H9") (pintype "bidirectional"))
    )
    (net (code "130") (name "unconnected-(REFX3-P4.1-PadH8)") (class "Default")
      (node (ref "REFX3") (pin "H8") (pinfunction "P4.1_H8") (pintype "bidirectional"))
    )
    (net (code "131") (name "unconnected-(REFX3-P4.2-PadG7)") (class "Default")
      (node (ref "REFX3") (pin "G7") (pinfunction "P4.2_G7") (pintype "bidirectional"))
    )
    (net (code "132") (name "unconnected-(REFX3-P4.3-PadG8)") (class "Default")
      (node (ref "REFX3") (pin "G8") (pinfunction "P4.3_G8") (pintype "bidirectional"))
    )
    (net (code "133") (name "unconnected-(REFX3-P4.4-PadG9)") (class "Default")
      (node (ref "REFX3") (pin "G9") (pinfunction "P4.4_G9") (pintype "bidirectional"))
    )
    (net (code "134") (name "unconnected-(REFX3-P4.5-PadF7)") (class "Default")
      (node (ref "REFX3") (pin "F7") (pinfunction "P4.5_F7") (pintype "bidirectional"))
    )
    (net (code "135") (name "unconnected-(REFX3-P4.6-PadF8)") (class "Default")
      (node (ref "REFX3") (pin "F8") (pinfunction "P4.6_F8") (pintype "bidirectional"))
    )
    (net (code "136") (name "unconnected-(REFX3-P4.7-PadF9)") (class "Default")
      (node (ref "REFX3") (pin "F9") (pinfunction "P4.7_F9") (pintype "bidirectional"))
    )
    (net (code "137") (name "unconnected-(REFX3-P5.0-PadE7)") (class "Default")
      (node (ref "REFX3") (pin "E7") (pinfunction "P5.0_E7") (pintype "bidirectional"))
    )
    (net (code "138") (name "unconnected-(REFX3-P5.1-PadE8)") (class "Default")
      (node (ref "REFX3") (pin "E8") (pinfunction "P5.1_E8") (pintype "bidirectional"))
    )
    (net (code "139") (name "unconnected-(REFX3-P5.2-PadE9)") (class "Default")
      (node (ref "REFX3") (pin "E9") (pinfunction "P5.2_E9") (pintype "bidirectional"))
    )
    (net (code "140") (name "unconnected-(REFX3-P5.3-PadD7)") (class "Default")
      (node (ref "REFX3") (pin "D7") (pinfunction "P5.3_D7") (pintype "bidirectional"))
    )
    (net (code "141") (name "unconnected-(REFX3-P5.4-PadD8)") (class "Default")
      (node (ref "REFX3") (pin "D8") (pinfunction "P5.4_D8") (pintype "bidirectional"))
    )
    (net (code "142") (name "unconnected-(REFX3-P5.5-PadC8)") (class "Default")
      (node (ref "REFX3") (pin "C8") (pinfunction "P5.5_C8") (pintype "bidirectional"))
    )
    (net (code "143") (name "unconnected-(REFX3-P5.6-PadD9)") (class "Default")
      (node (ref "REFX3") (pin "D9") (pinfunction "P5.6_D9") (pintype "bidirectional"))
    )
    (net (code "144") (name "unconnected-(REFX3-P5.7-PadC9)") (class "Default")
      (node (ref "REFX3") (pin "C9") (pinfunction "P5.7_C9") (pintype "bidirectional"))
    )
    (net (code "145") (name "unconnected-(REFX3-P6.0-PadJ9)") (class "Default")
      (node (ref "REFX3") (pin "J9") (pinfunction "P6.0_J9") (pintype "bidirectional"))
    )
    (net (code "146") (name "unconnected-(REFX3-P6.1-PadH7)") (class "Default")
      (node (ref "REFX3") (pin "H7") (pinfunction "P6.1_H7") (pintype "bidirectional"))
    )
    (net (code "147") (name "unconnected-(REFX3-P6.2-PadA9)") (class "Default")
      (node (ref "REFX3") (pin "A9") (pinfunction "P6.2_A9") (pintype "bidirectional"))
    )
    (net (code "148") (name "unconnected-(REFX3-P6.3-PadB9)") (class "Default")
      (node (ref "REFX3") (pin "B9") (pinfunction "P6.3_B9") (pintype "bidirectional"))
    )
    (net (code "149") (name "unconnected-(REFX3-P6.4-PadA8)") (class "Default")
      (node (ref "REFX3") (pin "A8") (pinfunction "P6.4_A8") (pintype "bidirectional"))
    )
    (net (code "150") (name "unconnected-(REFX3-P6.5-PadA7)") (class "Default")
      (node (ref "REFX3") (pin "A7") (pinfunction "P6.5_A7") (pintype "bidirectional"))
    )
    (net (code "151") (name "unconnected-(REFX3-P6.6-PadB8)") (class "Default")
      (node (ref "REFX3") (pin "B8") (pinfunction "P6.6_B8") (pintype "bidirectional"))
    )
    (net (code "152") (name "unconnected-(REFX3-P6.7-PadB7)") (class "Default")
      (node (ref "REFX3") (pin "B7") (pinfunction "P6.7_B7") (pintype "bidirectional"))
    )
    (net (code "153") (name "unconnected-(REFX3-P7.0-PadB5)") (class "Default")
      (node (ref "REFX3") (pin "B5") (pinfunction "P7.0_B5") (pintype "bidirectional"))
    )
    (net (code "154") (name "unconnected-(REFX3-P7.1-PadC5)") (class "Default")
      (node (ref "REFX3") (pin "C5") (pinfunction "P7.1_C5") (pintype "bidirectional"))
    )
    (net (code "155") (name "unconnected-(REFX3-P7.2-PadB4)") (class "Default")
      (node (ref "REFX3") (pin "B4") (pinfunction "P7.2_B4") (pintype "bidirectional"))
    )
    (net (code "156") (name "unconnected-(REFX3-P7.3-PadA4)") (class "Default")
      (node (ref "REFX3") (pin "A4") (pinfunction "P7.3_A4") (pintype "bidirectional"))
    )
    (net (code "157") (name "unconnected-(REFX3-P7.4-PadJ1)") (class "Default")
      (node (ref "REFX3") (pin "J1") (pinfunction "P7.4_J1") (pintype "bidirectional"))
    )
    (net (code "158") (name "unconnected-(REFX3-P7.5-PadH2)") (class "Default")
      (node (ref "REFX3") (pin "H2") (pinfunction "P7.5_H2") (pintype "bidirectional"))
    )
    (net (code "159") (name "unconnected-(REFX3-P7.6-PadJ2)") (class "Default")
      (node (ref "REFX3") (pin "J2") (pinfunction "P7.6_J2") (pintype "bidirectional"))
    )
    (net (code "160") (name "unconnected-(REFX3-P7.7-PadG3)") (class "Default")
      (node (ref "REFX3") (pin "G3") (pinfunction "P7.7_G3") (pintype "bidirectional"))
    )
    (net (code "161") (name "unconnected-(REFX3-P8.0-PadH3)") (class "Default")
      (node (ref "REFX3") (pin "H3") (pinfunction "P8.0_H3") (pintype "bidirectional"))
    )
    (net (code "162") (name "unconnected-(REFX3-P8.1-PadG4)") (class "Default")
      (node (ref "REFX3") (pin "G4") (pinfunction "P8.1_G4") (pintype "bidirectional"))
    )
    (net (code "163") (name "unconnected-(REFX3-PJ.0-PadJ6)") (class "Default")
      (node (ref "REFX3") (pin "J6") (pinfunction "PJ.0_J6") (pintype "bidirectional"))
    )
    (net (code "164") (name "unconnected-(REFX3-PJ.1-PadJ7)") (class "Default")
      (node (ref "REFX3") (pin "J7") (pinfunction "PJ.1_J7") (pintype "bidirectional"))
    )
    (net (code "165") (name "unconnected-(REFX3-PJ.2-PadA6)") (class "Default")
      (node (ref "REFX3") (pin "A6") (pinfunction "PJ.2_A6") (pintype "bidirectional"))
    )
    (net (code "166") (name "unconnected-(REFX3-PJ.3-PadA5)") (class "Default")
      (node (ref "REFX3") (pin "A5") (pinfunction "PJ.3_A5") (pintype "bidirectional"))
    )
    (net (code "167") (name "unconnected-(REFX3-PJ.4-PadB3)") (class "Default")
      (node (ref "REFX3") (pin "B3") (pinfunction "PJ.4_B3") (pintype "bidirectional"))
    )
    (net (code "168") (name "unconnected-(REFX3-PJ.5-PadA3)") (class "Default")
      (node (ref "REFX3") (pin "A3") (pinfunction "PJ.5_A3") (pintype "bidirectional"))
    )
    (net (code "169") (name "unconnected-(REFX3-RSTN{slash}NMI-PadB6)") (class "Default")
      (node (ref "REFX3") (pin "B6") (pinfunction "RSTN/NMI_B6") (pintype "bidirectional"))
    )
    (net (code "170") (name "unconnected-(REFX3-SWCLKTCK-PadA2)") (class "Default")
      (node (ref "REFX3") (pin "A2") (pinfunction "SWCLKTCK_A2") (pintype "bidirectional"))
    )
    (net (code "171") (name "unconnected-(REFX3-SWDIOTMS-PadB2)") (class "Default")
      (node (ref "REFX3") (pin "B2") (pinfunction "SWDIOTMS_B2") (pintype "bidirectional"))
    )
    (net (code "172") (name "unconnected-(REFX4-D-Pad3)") (class "Default")
      (node (ref "REFX4") (pin "3") (pinfunction "D_3") (pintype "passive"))
    )
    (net (code "173") (name "unconnected-(REFX4-G-Pad1)") (class "Default")
      (node (ref "REFX4") (pin "1") (pinfunction "G_1") (pintype "passive"))
    )
    (net (code "174") (name "unconnected-(REFX4-S-Pad2)") (class "Default")
      (node (ref "REFX4") (pin "2") (pinfunction "S_2") (pintype "passive"))
    )
    (net (code "175") (name "unconnected-(U2-~{CTS}-Pad5)") (class "Default")
      (node (ref "U2") (pin "5") (pinfunction "~{CTS}_5") (pintype "input"))
    )
  )
)
